# controller.net
KiCad netlist of a schematic drawn in EAGLE
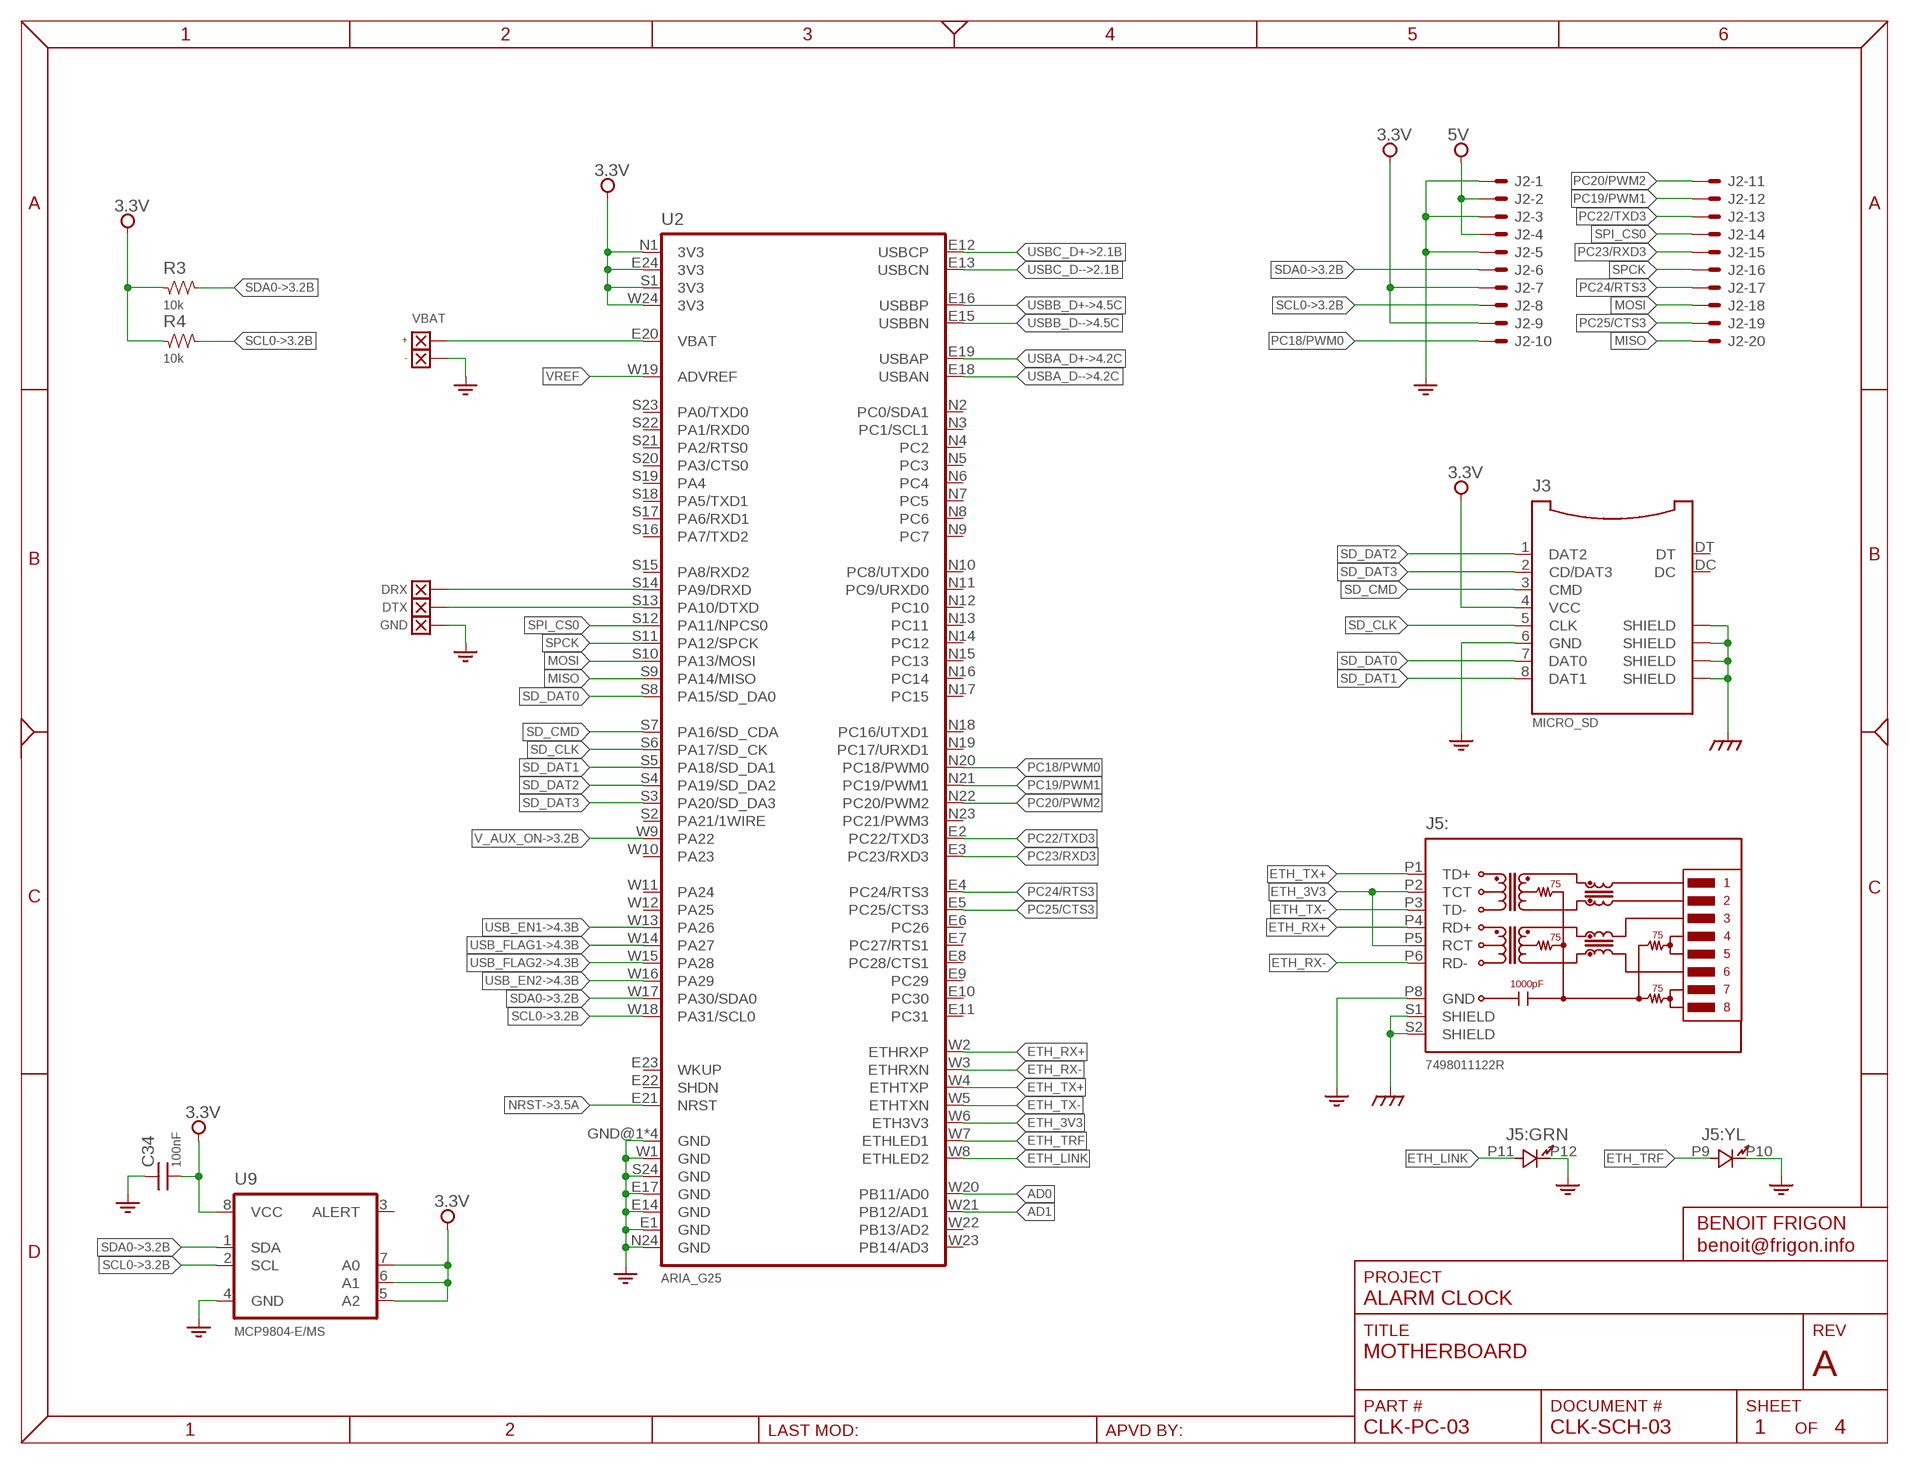
[diagram p0: schematic, sheet 1]
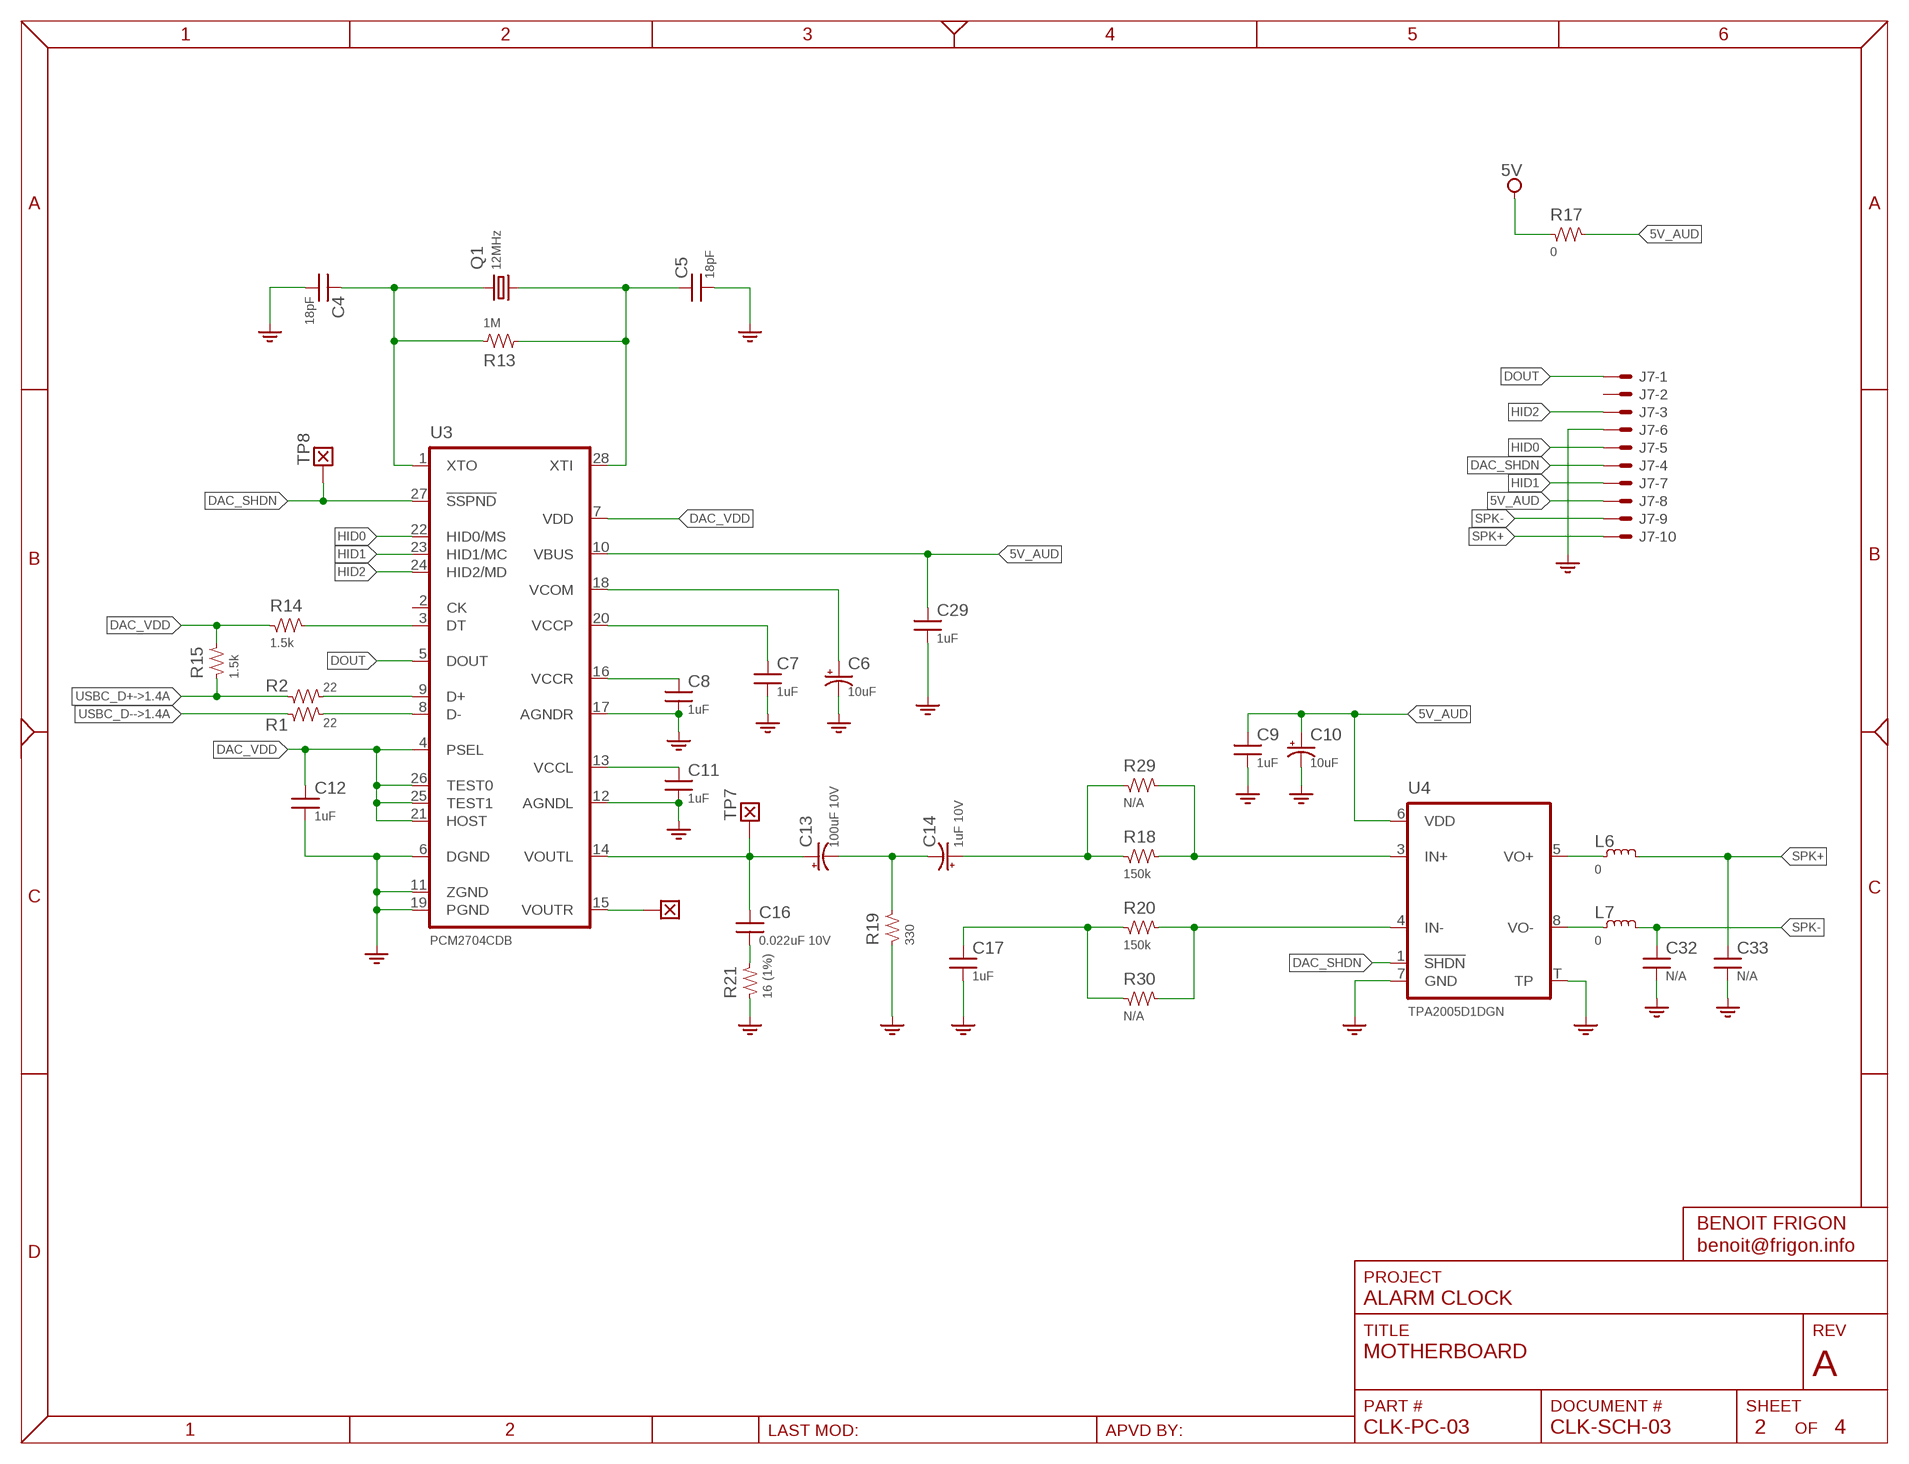
[diagram p1: schematic, sheet 2]
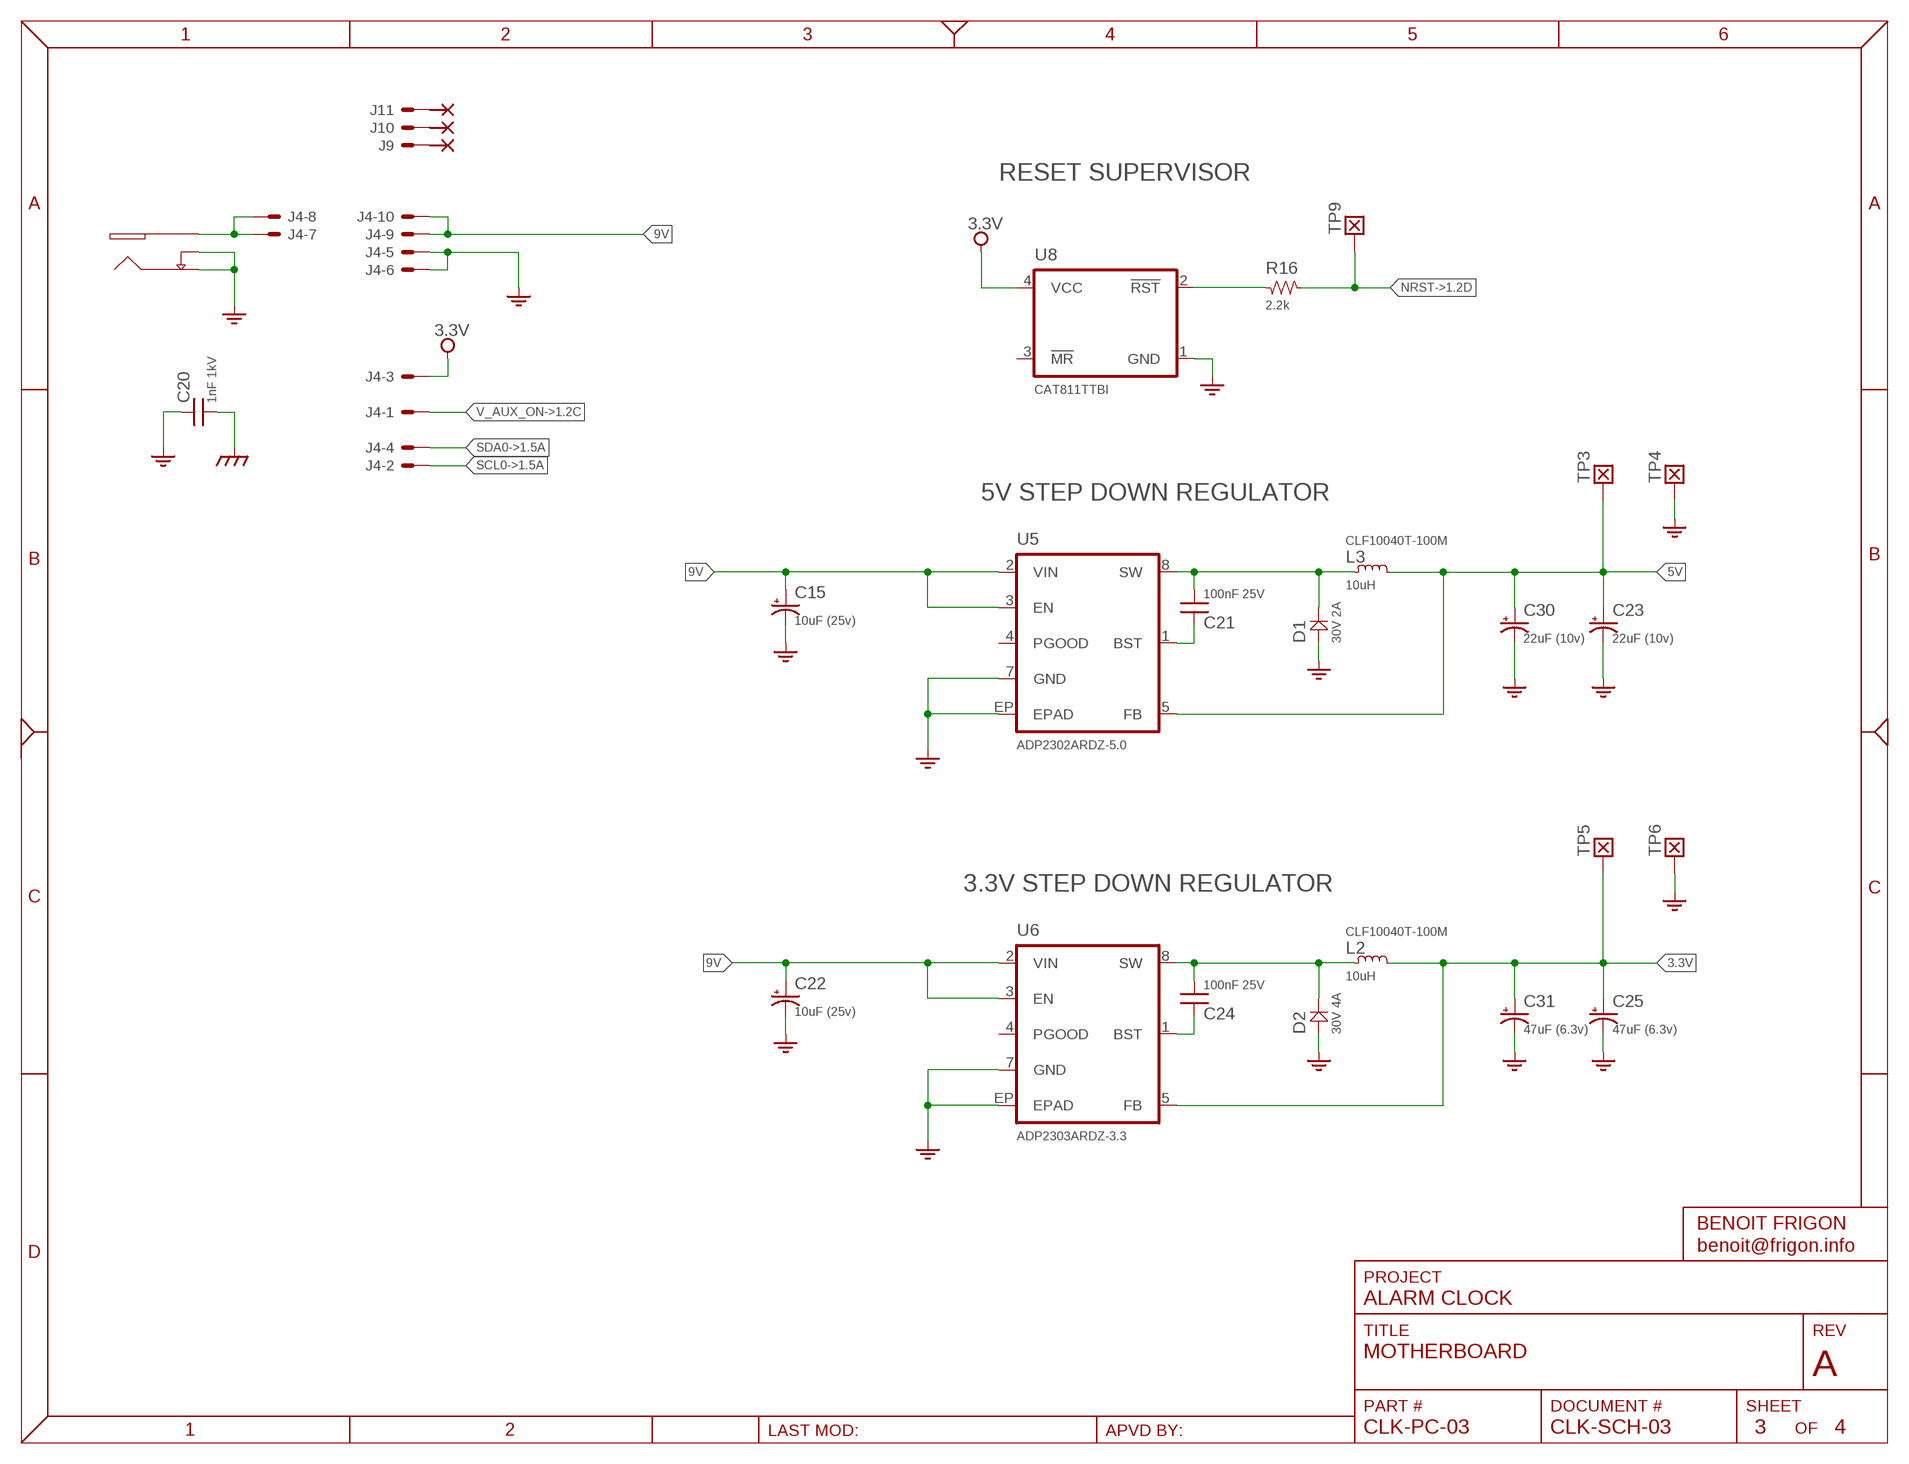
[diagram p2: schematic, sheet 3]
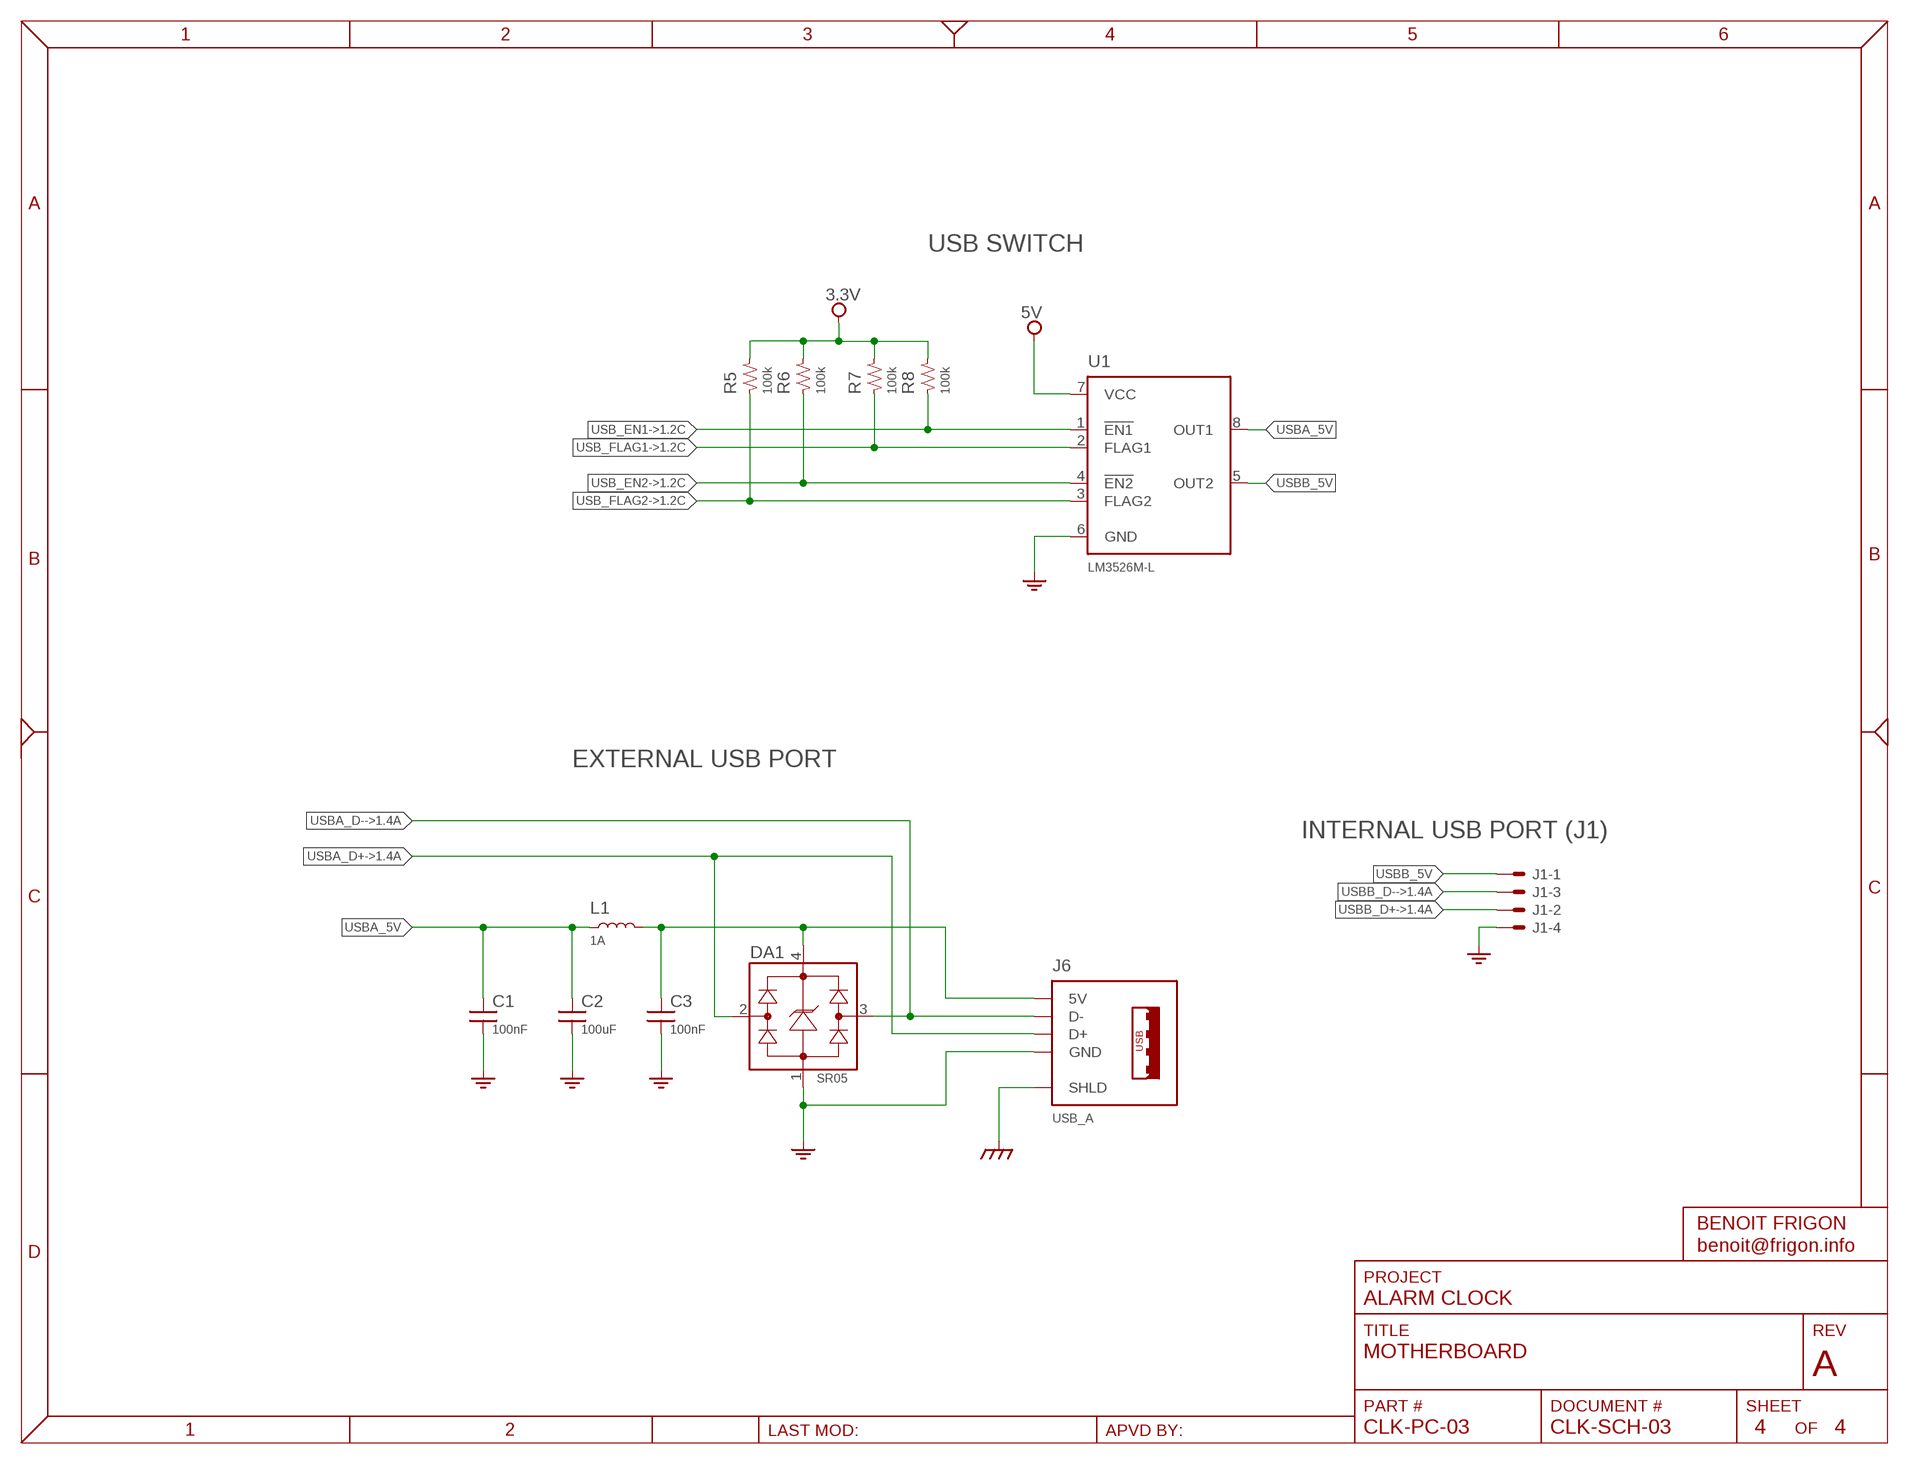
[diagram p3: schematic, sheet 4]

(export (version "E")
  (design (tool "Eeschema 10.0.6"))
  (components
    (comp (ref "C4")
      (value "18pF")
      (footprint "eagle-import:SMD_0603")
      (description "{DESCRIPTION} - SMT 0603 - {value}")
      (fields (field (name "PACKAGE") "SMT 0603"))
      (libsource (lib "eagle-import") (part "CAP-0603"))
    )
    (comp (ref "C5")
      (value "18pF")
      (footprint "eagle-import:SMD_0603")
      (libsource (lib "eagle-import") (part "CAP-0603"))
    )
    (comp (ref "C6")
      (value "10uF")
      (footprint "eagle-import:CAP_S0805")
      (description "Aluminium capacitor - SMT 0805 - {VALUE}")
      (libsource (lib "eagle-import") (part "CAP-E-?-0805ALUM"))
    )
    (comp (ref "C7")
      (value "1uF")
      (footprint "eagle-import:SMD_0603")
      (libsource (lib "eagle-import") (part "CAP-0603"))
    )
    (comp (ref "C8")
      (value "1uF")
      (footprint "eagle-import:SMD_0603")
      (description "{DESCRIPTION} - SMT 0603 - {value}")
      (fields (field (name "PACKAGE") "SMT 0603"))
      (libsource (lib "eagle-import") (part "CAP-0603"))
    )
    (comp (ref "C9")
      (value "1uF")
      (footprint "eagle-import:SMD_0603")
      (libsource (lib "eagle-import") (part "CAP-0603"))
    )
    (comp (ref "C10")
      (value "10uF")
      (footprint "eagle-import:CAP_S0805")
      (description "Aluminium capacitor - SMT 0805 - {VALUE}")
      (libsource (lib "eagle-import") (part "CAP-E-?-0805ALUM"))
    )
    (comp (ref "C11")
      (value "1uF")
      (footprint "eagle-import:SMD_0603")
      (description "{DESCRIPTION} - SMT 0603 - {value}")
      (fields (field (name "PACKAGE") "SMT 0603"))
      (libsource (lib "eagle-import") (part "CAP-0603"))
    )
    (comp (ref "C12")
      (value "1uF")
      (footprint "eagle-import:SMD_0603")
      (libsource (lib "eagle-import") (part "CAP-0603"))
    )
    (comp (ref "C13")
      (value "100uF 10V")
      (footprint "eagle-import:CAP_S1210")
      (description "Aluminium capacitor - SMT 1210 - {VALUE}")
      (fields (field (name "MFG") "AVX"))
      (libsource (lib "eagle-import") (part "CAP-E-?-1210ALUM"))
    )
    (comp (ref "C14")
      (value "1uF 10V")
      (footprint "eagle-import:CAP_S0805")
      (description "Aluminium capacitor - SMT 0805 - {VALUE}")
      (libsource (lib "eagle-import") (part "CAP-E-?-0805ALUM"))
    )
    (comp (ref "C16")
      (value "0.022uF 10V")
      (footprint "eagle-import:SMD_0603")
      (libsource (lib "eagle-import") (part "CAP-0603"))
    )
    (comp (ref "C17")
      (value "1uF")
      (footprint "eagle-import:SMD_0603")
      (libsource (lib "eagle-import") (part "CAP-0603"))
    )
    (comp (ref "C29")
      (value "1uF")
      (footprint "eagle-import:SMD_0603")
      (libsource (lib "eagle-import") (part "CAP-0603"))
    )
    (comp (ref "C32")
      (value "N/A")
      (footprint "eagle-import:SMD_0603")
      (libsource (lib "eagle-import") (part "CAP-0603"))
    )
    (comp (ref "C33")
      (value "N/A")
      (footprint "eagle-import:SMD_0603")
      (libsource (lib "eagle-import") (part "CAP-0603"))
    )
    (comp (ref "J7")
      (value "DL-1.25MM-HEADER-10")
      (footprint "eagle-import:DF13A-10DP-1.25")
      (libsource (lib "eagle-import") (part "DL-1.25MM-HEADER-10"))
    )
    (comp (ref "L6")
      (value "0")
      (footprint "eagle-import:SMD_0603")
      (description "{DESCRIPTION} - SMT 0603 - {VALUE}")
      (libsource (lib "eagle-import") (part "IND?-0603"))
    )
    (comp (ref "L7")
      (value "0")
      (footprint "eagle-import:SMD_0603")
      (description "{DESCRIPTION} - SMT 0603 - {VALUE}")
      (libsource (lib "eagle-import") (part "IND?-0603"))
    )
    (comp (ref "Q1")
      (value "12MHz")
      (footprint "eagle-import:HC49UP")
      (libsource (lib "eagle-import") (part "XTALHC49UP"))
    )
    (comp (ref "R1")
      (value "22")
      (footprint "eagle-import:SMD_0603")
      (libsource (lib "eagle-import") (part "RES-0603"))
    )
    (comp (ref "R2")
      (value "22")
      (footprint "eagle-import:SMD_0603")
      (libsource (lib "eagle-import") (part "RES-0603"))
    )
    (comp (ref "R13")
      (value "1M")
      (footprint "eagle-import:SMD_0603")
      (libsource (lib "eagle-import") (part "RES-0603"))
    )
    (comp (ref "R14")
      (value "1.5k")
      (footprint "eagle-import:SMD_0603")
      (libsource (lib "eagle-import") (part "RES-0603"))
    )
    (comp (ref "R15")
      (value "1.5k")
      (footprint "eagle-import:SMD_0603")
      (libsource (lib "eagle-import") (part "RES-0603"))
    )
    (comp (ref "R17")
      (value "0")
      (footprint "eagle-import:SMD_1206")
      (libsource (lib "eagle-import") (part "RES-1206"))
    )
    (comp (ref "R18")
      (value "150k")
      (footprint "eagle-import:SMD_0603")
      (libsource (lib "eagle-import") (part "RES-0603"))
    )
    (comp (ref "R19")
      (value "330")
      (footprint "eagle-import:SMD_0603")
      (libsource (lib "eagle-import") (part "RES-0603"))
    )
    (comp (ref "R20")
      (value "150k")
      (footprint "eagle-import:SMD_0603")
      (description "{DESCRIPTION} - SMT 0603 - {VALUE}")
      (fields (field (name "PACKAGE") "SMT 0603"))
      (libsource (lib "eagle-import") (part "RES-0603"))
    )
    (comp (ref "R21")
      (value "16 (1%)")
      (footprint "eagle-import:SMD_0603")
      (libsource (lib "eagle-import") (part "RES-0603"))
    )
    (comp (ref "R29")
      (value "N/A")
      (footprint "eagle-import:SMD_0603")
      (description "{DESCRIPTION} - SMT 0603 - {VALUE}")
      (fields (field (name "PACKAGE") "SMT 0603"))
      (libsource (lib "eagle-import") (part "RES-0603"))
    )
    (comp (ref "R30")
      (value "N/A")
      (footprint "eagle-import:SMD_0603")
      (description "{DESCRIPTION} - SMT 0603 - {VALUE}")
      (fields (field (name "PACKAGE") "SMT 0603"))
      (libsource (lib "eagle-import") (part "RES-0603"))
    )
    (comp (ref "TP7")
      (value "TEST_POINT-050")
      (footprint "eagle-import:TP_050")
      (libsource (lib "eagle-import") (part "TEST_POINT-050"))
    )
    (comp (ref "TP8")
      (value "TEST_POINT-050")
      (footprint "eagle-import:TP_050")
      (libsource (lib "eagle-import") (part "TEST_POINT-050"))
    )
    (comp (ref "U3")
      (value "PCM2704CDB")
      (footprint "eagle-import:SSOP28")
      (libsource (lib "eagle-import") (part "PCM2704CDB"))
    )
    (comp (ref "U4")
      (value "TPA2005D1DGN")
      (footprint "eagle-import:PPSOP8")
      (libsource (lib "eagle-import") (part "TPA2005D1?DGN"))
    )
    (comp (ref "W1")
      (value "WIRE-150X75")
      (footprint "eagle-import:WIRE_SMT_150X75")
      (libsource (lib "eagle-import") (part "WIRE-?150X75"))
    )
    (comp (ref "C15")
      (value "10uF (25v)")
      (footprint "eagle-import:CAP_S1210")
      (fields (field (name "MFG") "AVX") (field (name "PART_NO") "TPSB106K025R1800"))
      (libsource (lib "eagle-import") (part "CAP-E-?-1210TANT"))
    )
    (comp (ref "C20")
      (value "1nF 1kV")
      (footprint "eagle-import:SMD_0805")
      (libsource (lib "eagle-import") (part "CAP-0805"))
    )
    (comp (ref "C21")
      (value "100nF 25V")
      (footprint "eagle-import:SMD_0603")
      (libsource (lib "eagle-import") (part "CAP-0603"))
    )
    (comp (ref "C22")
      (value "10uF (25v)")
      (footprint "eagle-import:CAP_S1210")
      (fields (field (name "MFG") "AVX") (field (name "PART_NO") "TPSB106K025R1800"))
      (libsource (lib "eagle-import") (part "CAP-E-?-1210TANT"))
    )
    (comp (ref "C23")
      (value "22uF (10v)")
      (footprint "eagle-import:CAP_S1206")
      (description "Tantalum capacitor - SMT 1206 - {VALUE}")
      (fields (field (name "MFG") "AVX") (field (name "PART_NO") "TPSA226M010R0900"))
      (libsource (lib "eagle-import") (part "CAP-E-?-1206TANT"))
    )
    (comp (ref "C24")
      (value "100nF 25V")
      (footprint "eagle-import:SMD_0603")
      (libsource (lib "eagle-import") (part "CAP-0603"))
    )
    (comp (ref "C25")
      (value "47uF (6.3v)")
      (footprint "eagle-import:CAP_S1206")
      (description "Tantalum capacitor - SMT 1206 - {VALUE}")
      (fields (field (name "MFG") "AVX") (field (name "PART_NO") "TPSA476K006R0800"))
      (libsource (lib "eagle-import") (part "CAP-E-?-1206TANT"))
    )
    (comp (ref "C30")
      (value "22uF (10v)")
      (footprint "eagle-import:CAP_S1206")
      (description "Tantalum capacitor - SMT 1206 - {VALUE}")
      (fields (field (name "MFG") "AVX") (field (name "PART_NO") "TPSA226M010R0900"))
      (libsource (lib "eagle-import") (part "CAP-E-?-1206TANT"))
    )
    (comp (ref "C31")
      (value "47uF (6.3v)")
      (footprint "eagle-import:CAP_S1206")
      (description "Tantalum capacitor - SMT 1206 - {VALUE}")
      (fields (field (name "MFG") "AVX") (field (name "PART_NO") "TPSA476K006R0800"))
      (libsource (lib "eagle-import") (part "CAP-E-?-1206TANT"))
    )
    (comp (ref "D1")
      (value "30V 2A")
      (footprint "eagle-import:DIODE_DO214-AA")
      (libsource (lib "eagle-import") (part "DIODE-DO214-AA"))
    )
    (comp (ref "D2")
      (value "30V 4A")
      (footprint "eagle-import:DIODE_DO214-AA")
      (libsource (lib "eagle-import") (part "DIODE-DO214-AA"))
    )
    (comp (ref "J4")
      (value "DL-100-HEADER-10-V")
      (footprint "eagle-import:534206-5")
      (description "{DESCRIPTION} Receptacle - Vertical")
      (fields (field (name "MFG") "Tyco Electronics") (field (name "SKU") "534206-5"))
      (libsource (lib "eagle-import") (part "DL-100-HEADER-10-V"))
    )
    (comp (ref "J8")
      (value "CUI-PJ-013C")
      (footprint "eagle-import:CUI-PJ-013C")
      (libsource (lib "eagle-import") (part "CUI-PJ-013C"))
    )
    (comp (ref "J9")
      (value "SNG-100-HEADER-01-HDR-V")
      (footprint "eagle-import:HDR_M_1")
      (libsource (lib "eagle-import") (part "SNG-100-HEADER-01-HDR-V"))
    )
    (comp (ref "J10")
      (value "SNG-100-HEADER-01-HDR-V")
      (footprint "eagle-import:HDR_M_1")
      (libsource (lib "eagle-import") (part "SNG-100-HEADER-01-HDR-V"))
    )
    (comp (ref "J11")
      (value "SNG-100-HEADER-01-HDR-V")
      (footprint "eagle-import:HDR_M_1")
      (libsource (lib "eagle-import") (part "SNG-100-HEADER-01-HDR-V"))
    )
    (comp (ref "L2")
      (value "10uH")
      (footprint "eagle-import:IND-10X10")
      (fields (field (name "PART_NO") "CLF10040T-100M"))
      (libsource (lib "eagle-import") (part "IND?-10X10"))
    )
    (comp (ref "L3")
      (value "10uH")
      (footprint "eagle-import:IND-10X10")
      (fields (field (name "MFG") "TDK") (field (name "PART_NO") "CLF10040T-100M"))
      (libsource (lib "eagle-import") (part "IND?-10X10"))
    )
    (comp (ref "R16")
      (value "2.2k")
      (footprint "eagle-import:SMD_0603")
      (libsource (lib "eagle-import") (part "RES-0603"))
    )
    (comp (ref "TP3")
      (value "TEST_POINT-050")
      (footprint "eagle-import:TP_050")
      (libsource (lib "eagle-import") (part "TEST_POINT-050"))
    )
    (comp (ref "TP4")
      (value "TEST_POINT-050")
      (footprint "eagle-import:TP_050")
      (libsource (lib "eagle-import") (part "TEST_POINT-050"))
    )
    (comp (ref "TP5")
      (value "TEST_POINT-050")
      (footprint "eagle-import:TP_050")
      (fields (field (name "BOM") "FALSE"))
      (libsource (lib "eagle-import") (part "TEST_POINT-050"))
    )
    (comp (ref "TP6")
      (value "TEST_POINT-050")
      (footprint "eagle-import:TP_050")
      (fields (field (name "BOM") "FALSE"))
      (libsource (lib "eagle-import") (part "TEST_POINT-050"))
    )
    (comp (ref "TP9")
      (value "TEST_POINT-050")
      (footprint "eagle-import:TP_050")
      (libsource (lib "eagle-import") (part "TEST_POINT-050"))
    )
    (comp (ref "U5")
      (value "ADP2302ARDZ-5.0")
      (footprint "eagle-import:SOIC8-EP")
      (description "{DESCRIPTION} - 2A, 5V")
      (fields (field (name "MFG") "Analog Devices"))
      (libsource (lib "eagle-import") (part "ADP230?2ARDZ-5.0"))
    )
    (comp (ref "U6")
      (value "ADP2303ARDZ-3.3")
      (footprint "eagle-import:SOIC8-EP")
      (description "{DESCRIPTION} - 3A, 3.3v")
      (fields (field (name "MFG") "Analog Devices"))
      (libsource (lib "eagle-import") (part "ADP230?3ARDZ-3.3"))
    )
    (comp (ref "U8")
      (value "CAT811TTBI")
      (footprint "eagle-import:SOT143")
      (description "{DESCRIPTION} - 3.08V threshold")
      (fields (field (name "MFG") "ON Semiconductors"))
      (libsource (lib "eagle-import") (part "CAT811?TBIT"))
    )
    (comp (ref "C34")
      (value "100nF")
      (footprint "eagle-import:SMD_0603")
      (libsource (lib "eagle-import") (part "CAP-0603"))
    )
    (comp (ref "J2")
      (value "DL-1.25MM-HEADER-20")
      (footprint "eagle-import:DF13A-20DP-1.25")
      (libsource (lib "eagle-import") (part "DL-1.25MM-HEADER-20"))
    )
    (comp (ref "J3")
      (value "MICRO_SD")
      (footprint "eagle-import:5027020891")
      (libsource (lib "eagle-import") (part "MICRO_SD"))
    )
    (comp (ref "J5")
      (value "7498011122R")
      (footprint "eagle-import:7498011122R")
      (libsource (lib "eagle-import") (part "7498011122R"))
    )
    (comp (ref "R3")
      (value "10k")
      (footprint "eagle-import:SMD_0603")
      (description "{DESCRIPTION} - SMT 0603 - {VALUE}")
      (fields (field (name "PACKAGE") "SMT 0603"))
      (libsource (lib "eagle-import") (part "RES-0603"))
    )
    (comp (ref "R4")
      (value "10k")
      (footprint "eagle-import:SMD_0603")
      (description "{DESCRIPTION} - SMT 0603 - {VALUE}")
      (fields (field (name "PACKAGE") "SMT 0603"))
      (libsource (lib "eagle-import") (part "RES-0603"))
    )
    (comp (ref "TP1")
      (value "+")
      (footprint "eagle-import:WIRE_SMT_150X75")
      (libsource (lib "eagle-import") (part "WIRE-?150X75"))
    )
    (comp (ref "TP2")
      (value "-")
      (footprint "eagle-import:WIRE_SMT_150X75")
      (libsource (lib "eagle-import") (part "WIRE-?150X75"))
    )
    (comp (ref "U2")
      (value "ARIA_G25")
      (footprint "eagle-import:ARIA_G25")
      (libsource (lib "eagle-import") (part "ARIA_G25"))
    )
    (comp (ref "U9")
      (value "MCP9804-E/MS")
      (footprint "eagle-import:MSOP8")
      (fields (field (name "MFG") "Microchip"))
      (libsource (lib "eagle-import") (part "MCP9804-/?MSE"))
    )
    (comp (ref "W2")
      (value "DRX")
      (footprint "eagle-import:WIRE_SMT_150X75")
      (libsource (lib "eagle-import") (part "WIRE-?150X75"))
    )
    (comp (ref "W3")
      (value "DTX")
      (footprint "eagle-import:WIRE_SMT_150X75")
      (libsource (lib "eagle-import") (part "WIRE-?150X75"))
    )
    (comp (ref "W4")
      (value "GND")
      (footprint "eagle-import:WIRE_SMT_150X75")
      (libsource (lib "eagle-import") (part "WIRE-?150X75"))
    )
    (comp (ref "C1")
      (value "100nF")
      (footprint "eagle-import:SMD_0603")
      (libsource (lib "eagle-import") (part "CAP-0603"))
    )
    (comp (ref "C2")
      (value "100uF")
      (footprint "eagle-import:SMD_0805")
      (libsource (lib "eagle-import") (part "CAP-0805"))
    )
    (comp (ref "C3")
      (value "100nF")
      (footprint "eagle-import:SMD_0603")
      (libsource (lib "eagle-import") (part "CAP-0603"))
    )
    (comp (ref "DA1")
      (value "SR05")
      (footprint "eagle-import:SOT143")
      (fields (field (name "MFG") "Semtech"))
      (libsource (lib "eagle-import") (part "SR05"))
    )
    (comp (ref "J1")
      (value "SNG-2MM-HEADER-04-V")
      (footprint "eagle-import:DF3X-4P-2DSA")
      (description "{DESCRIPTION} - Vertical")
      (fields (field (name "MFG") "Hirose Electronic") (field (name "SKU") "DF3A-4P-2DSA"))
      (libsource (lib "eagle-import") (part "SNG-2MM-HEADER-04-V"))
    )
    (comp (ref "J6")
      (value "USB_A")
      (footprint "eagle-import:292303-1")
      (libsource (lib "eagle-import") (part "USB_A"))
    )
    (comp (ref "L1")
      (value "1A")
      (footprint "eagle-import:SMD_0805")
      (libsource (lib "eagle-import") (part "FERRITE"))
    )
    (comp (ref "R5")
      (value "100k")
      (footprint "eagle-import:SMD_0603")
      (description "{DESCRIPTION} - SMT 0603 - {VALUE}")
      (fields (field (name "PACKAGE") "SMT 0603"))
      (libsource (lib "eagle-import") (part "RES-0603"))
    )
    (comp (ref "R6")
      (value "100k")
      (footprint "eagle-import:SMD_0603")
      (description "{DESCRIPTION} - SMT 0603 - {VALUE}")
      (fields (field (name "PACKAGE") "SMT 0603"))
      (libsource (lib "eagle-import") (part "RES-0603"))
    )
    (comp (ref "R7")
      (value "100k")
      (footprint "eagle-import:SMD_0603")
      (description "{DESCRIPTION} - SMT 0603 - {VALUE}")
      (fields (field (name "PACKAGE") "SMT 0603"))
      (libsource (lib "eagle-import") (part "RES-0603"))
    )
    (comp (ref "R8")
      (value "100k")
      (footprint "eagle-import:SMD_0603")
      (description "{DESCRIPTION} - SMT 0603 - {VALUE}")
      (fields (field (name "PACKAGE") "SMT 0603"))
      (libsource (lib "eagle-import") (part "RES-0603"))
    )
    (comp (ref "U1")
      (value "LM3526M-L")
      (footprint "eagle-import:SOIC8")
      (fields (field (name "MFG") "National Semiconductors"))
      (libsource (lib "eagle-import") (part "LM3526?-ML"))
    )
  )
  (nets
    (net (code "1") (name "3.3V") (class "Default")
      (node (ref "C25") (pin "+") (pinfunction "+_+") (pintype "passive"))
      (node (ref "C31") (pin "+") (pinfunction "+_+") (pintype "passive"))
      (node (ref "C34") (pin "2") (pinfunction "2_2") (pintype "passive"))
      (node (ref "J2") (pin "7") (pinfunction "S_7") (pintype "bidirectional"))
      (node (ref "J2") (pin "9") (pinfunction "S_9") (pintype "bidirectional"))
      (node (ref "J3") (pin "4") (pinfunction "VCC_4") (pintype "power_in"))
      (node (ref "J4") (pin "3") (pinfunction "S_3") (pintype "bidirectional"))
      (node (ref "L2") (pin "2") (pinfunction "2_2") (pintype "passive"))
      (node (ref "R3") (pin "1") (pinfunction "1_1") (pintype "passive"))
      (node (ref "R4") (pin "1") (pinfunction "1_1") (pintype "passive"))
      (node (ref "R5") (pin "2") (pinfunction "2_2") (pintype "passive"))
      (node (ref "R6") (pin "2") (pinfunction "2_2") (pintype "passive"))
      (node (ref "R7") (pin "2") (pinfunction "2_2") (pintype "passive"))
      (node (ref "R8") (pin "2") (pinfunction "2_2") (pintype "passive"))
      (node (ref "TP5") (pin "1") (pinfunction "P$1_1") (pintype "bidirectional"))
      (node (ref "U2") (pin "E24") (pinfunction "3V3_E24") (pintype "power_in"))
      (node (ref "U2") (pin "N1") (pinfunction "3V3_N1") (pintype "power_in"))
      (node (ref "U2") (pin "S1") (pinfunction "3V3_S1") (pintype "power_in"))
      (node (ref "U2") (pin "W24") (pinfunction "3V3_W24") (pintype "power_in"))
      (node (ref "U6") (pin "5") (pinfunction "FB_5") (pintype "bidirectional"))
      (node (ref "U8") (pin "4") (pinfunction "VCC_4") (pintype "power_in"))
      (node (ref "U9") (pin "5") (pinfunction "A2_5") (pintype "bidirectional"))
      (node (ref "U9") (pin "6") (pinfunction "A1_6") (pintype "bidirectional"))
      (node (ref "U9") (pin "7") (pinfunction "A0_7") (pintype "bidirectional"))
      (node (ref "U9") (pin "8") (pinfunction "VCC_8") (pintype "power_in"))
    )
    (net (code "2") (name "5V") (class "Default")
      (node (ref "C23") (pin "+") (pinfunction "+_+") (pintype "passive"))
      (node (ref "C30") (pin "+") (pinfunction "+_+") (pintype "passive"))
      (node (ref "J2") (pin "2") (pinfunction "S_2") (pintype "bidirectional"))
      (node (ref "J2") (pin "4") (pinfunction "S_4") (pintype "bidirectional"))
      (node (ref "L3") (pin "2") (pinfunction "2_2") (pintype "passive"))
      (node (ref "R17") (pin "1") (pinfunction "1_1") (pintype "passive"))
      (node (ref "TP3") (pin "1") (pinfunction "P$1_1") (pintype "bidirectional"))
      (node (ref "U1") (pin "7") (pinfunction "VCC_7") (pintype "bidirectional"))
      (node (ref "U5") (pin "5") (pinfunction "FB_5") (pintype "bidirectional"))
    )
    (net (code "3") (name "5V_AUD") (class "Default")
      (node (ref "C10") (pin "+") (pinfunction "+_+") (pintype "passive"))
      (node (ref "C29") (pin "1") (pinfunction "1_1") (pintype "passive"))
      (node (ref "C9") (pin "1") (pinfunction "1_1") (pintype "passive"))
      (node (ref "J7") (pin "8") (pinfunction "S_8") (pintype "bidirectional"))
      (node (ref "R17") (pin "2") (pinfunction "2_2") (pintype "passive"))
      (node (ref "U3") (pin "10") (pinfunction "VBUS_10") (pintype "bidirectional"))
      (node (ref "U4") (pin "6") (pinfunction "VDD_6") (pintype "bidirectional"))
    )
    (net (code "4") (name "9V") (class "Default")
      (node (ref "C15") (pin "+") (pinfunction "+_+") (pintype "passive"))
      (node (ref "C22") (pin "+") (pinfunction "+_+") (pintype "passive"))
      (node (ref "J4") (pin "10") (pinfunction "S_10") (pintype "bidirectional"))
      (node (ref "J4") (pin "9") (pinfunction "S_9") (pintype "bidirectional"))
      (node (ref "U5") (pin "2") (pinfunction "VIN_2") (pintype "bidirectional"))
      (node (ref "U5") (pin "3") (pinfunction "EN_3") (pintype "bidirectional"))
      (node (ref "U6") (pin "2") (pinfunction "VIN_2") (pintype "bidirectional"))
      (node (ref "U6") (pin "3") (pinfunction "EN_3") (pintype "bidirectional"))
    )
    (net (code "5") (name "AD0") (class "Default")
      (node (ref "U2") (pin "W20") (pinfunction "PB11/AD0_W20") (pintype "bidirectional"))
    )
    (net (code "6") (name "AD1") (class "Default")
      (node (ref "U2") (pin "W21") (pinfunction "PB12/AD1_W21") (pintype "bidirectional"))
    )
    (net (code "7") (name "DAC_SHDN") (class "Default")
      (node (ref "J7") (pin "4") (pinfunction "S_4") (pintype "bidirectional"))
      (node (ref "TP8") (pin "1") (pinfunction "P$1_1") (pintype "bidirectional"))
      (node (ref "U3") (pin "27") (pinfunction "~{SSPND}_27") (pintype "bidirectional"))
      (node (ref "U4") (pin "1") (pinfunction "~{SHDN}_1") (pintype "bidirectional"))
    )
    (net (code "8") (name "DAC_VDD") (class "Default")
      (node (ref "C12") (pin "1") (pinfunction "1_1") (pintype "passive"))
      (node (ref "R14") (pin "1") (pinfunction "1_1") (pintype "passive"))
      (node (ref "R15") (pin "2") (pinfunction "2_2") (pintype "passive"))
      (node (ref "U3") (pin "21") (pinfunction "HOST_21") (pintype "bidirectional"))
      (node (ref "U3") (pin "25") (pinfunction "TEST1_25") (pintype "bidirectional"))
      (node (ref "U3") (pin "26") (pinfunction "TEST0_26") (pintype "bidirectional"))
      (node (ref "U3") (pin "4") (pinfunction "PSEL_4") (pintype "bidirectional"))
      (node (ref "U3") (pin "7") (pinfunction "VDD_7") (pintype "bidirectional"))
    )
    (net (code "9") (name "DOUT") (class "Default")
      (node (ref "J7") (pin "1") (pinfunction "S_1") (pintype "bidirectional"))
      (node (ref "U3") (pin "5") (pinfunction "DOUT_5") (pintype "bidirectional"))
    )
    (net (code "10") (name "EARTH") (class "Default")
      (node (ref "C20") (pin "2") (pinfunction "2_2") (pintype "passive"))
      (node (ref "J3") (pin "SHDL@3") (pinfunction "SHIELD_SHDL@3") (pintype "power_in"))
      (node (ref "J3") (pin "SHLD@1") (pinfunction "SHIELD_SHLD@1") (pintype "power_in"))
      (node (ref "J3") (pin "SHLD@2") (pinfunction "SHIELD_SHLD@2") (pintype "power_in"))
      (node (ref "J3") (pin "SHLD@4") (pinfunction "SHIELD_SHLD@4") (pintype "power_in"))
      (node (ref "J5") (pin "S1") (pinfunction "SHIELD_S1") (pintype "bidirectional"))
      (node (ref "J5") (pin "S2") (pinfunction "SHIELD_S2") (pintype "bidirectional"))
      (node (ref "J6") (pin "SHLD@1") (pinfunction "SHLD_SHLD@1") (pintype "bidirectional"))
      (node (ref "J6") (pin "SHLD@2") (pinfunction "SHLD_SHLD@2") (pintype "bidirectional"))
    )
    (net (code "11") (name "ETH_3V3") (class "Default")
      (node (ref "J5") (pin "P2") (pinfunction "TCT_P2") (pintype "bidirectional"))
      (node (ref "J5") (pin "P5") (pinfunction "RCT_P5") (pintype "bidirectional"))
      (node (ref "U2") (pin "W6") (pinfunction "ETH3V3_W6") (pintype "bidirectional"))
    )
    (net (code "12") (name "ETH_LINK") (class "Default")
      (node (ref "J5") (pin "P11") (pinfunction "A_P11") (pintype "bidirectional"))
      (node (ref "U2") (pin "W8") (pinfunction "ETHLED2_W8") (pintype "bidirectional"))
    )
    (net (code "13") (name "ETH_RX+") (class "Default")
      (node (ref "J5") (pin "P4") (pinfunction "RD+_P4") (pintype "bidirectional"))
      (node (ref "U2") (pin "W2") (pinfunction "ETHRXP_W2") (pintype "bidirectional"))
    )
    (net (code "14") (name "ETH_RX-") (class "Default")
      (node (ref "J5") (pin "P6") (pinfunction "RD-_P6") (pintype "bidirectional"))
      (node (ref "U2") (pin "W3") (pinfunction "ETHRXN_W3") (pintype "bidirectional"))
    )
    (net (code "15") (name "ETH_TRF") (class "Default")
      (node (ref "J5") (pin "P9") (pinfunction "A_P9") (pintype "bidirectional"))
      (node (ref "U2") (pin "W7") (pinfunction "ETHLED1_W7") (pintype "bidirectional"))
    )
    (net (code "16") (name "ETH_TX+") (class "Default")
      (node (ref "J5") (pin "P1") (pinfunction "TD+_P1") (pintype "bidirectional"))
      (node (ref "U2") (pin "W4") (pinfunction "ETHTXP_W4") (pintype "bidirectional"))
    )
    (net (code "17") (name "ETH_TX-") (class "Default")
      (node (ref "J5") (pin "P3") (pinfunction "TD-_P3") (pintype "bidirectional"))
      (node (ref "U2") (pin "W5") (pinfunction "ETHTXN_W5") (pintype "bidirectional"))
    )
    (net (code "18") (name "GND") (class "Default")
      (node (ref "C1") (pin "2") (pinfunction "2_2") (pintype "passive"))
      (node (ref "C10") (pin "-") (pinfunction "-_-") (pintype "passive"))
      (node (ref "C11") (pin "2") (pinfunction "2_2") (pintype "passive"))
      (node (ref "C12") (pin "2") (pinfunction "2_2") (pintype "passive"))
      (node (ref "C15") (pin "-") (pinfunction "-_-") (pintype "passive"))
      (node (ref "C17") (pin "2") (pinfunction "2_2") (pintype "passive"))
      (node (ref "C2") (pin "2") (pinfunction "2_2") (pintype "passive"))
      (node (ref "C20") (pin "1") (pinfunction "1_1") (pintype "passive"))
      (node (ref "C22") (pin "-") (pinfunction "-_-") (pintype "passive"))
      (node (ref "C23") (pin "-") (pinfunction "-_-") (pintype "passive"))
      (node (ref "C25") (pin "-") (pinfunction "-_-") (pintype "passive"))
      (node (ref "C29") (pin "2") (pinfunction "2_2") (pintype "passive"))
      (node (ref "C3") (pin "2") (pinfunction "2_2") (pintype "passive"))
      (node (ref "C30") (pin "-") (pinfunction "-_-") (pintype "passive"))
      (node (ref "C31") (pin "-") (pinfunction "-_-") (pintype "passive"))
      (node (ref "C32") (pin "2") (pinfunction "2_2") (pintype "passive"))
      (node (ref "C33") (pin "2") (pinfunction "2_2") (pintype "passive"))
      (node (ref "C34") (pin "1") (pinfunction "1_1") (pintype "passive"))
      (node (ref "C4") (pin "2") (pinfunction "2_2") (pintype "passive"))
      (node (ref "C5") (pin "2") (pinfunction "2_2") (pintype "passive"))
      (node (ref "C6") (pin "-") (pinfunction "-_-") (pintype "passive"))
      (node (ref "C7") (pin "2") (pinfunction "2_2") (pintype "passive"))
      (node (ref "C8") (pin "2") (pinfunction "2_2") (pintype "passive"))
      (node (ref "C9") (pin "2") (pinfunction "2_2") (pintype "passive"))
      (node (ref "D1") (pin "A") (pinfunction "A_A") (pintype "passive"))
      (node (ref "D2") (pin "A") (pinfunction "A_A") (pintype "passive"))
      (node (ref "DA1") (pin "1") (pinfunction "1_1") (pintype "passive"))
      (node (ref "J1") (pin "4") (pinfunction "S_4") (pintype "bidirectional"))
      (node (ref "J2") (pin "1") (pinfunction "S_1") (pintype "bidirectional"))
      (node (ref "J2") (pin "3") (pinfunction "S_3") (pintype "bidirectional"))
      (node (ref "J2") (pin "5") (pinfunction "S_5") (pintype "bidirectional"))
      (node (ref "J3") (pin "6") (pinfunction "GND_6") (pintype "power_in"))
      (node (ref "J4") (pin "5") (pinfunction "S_5") (pintype "bidirectional"))
      (node (ref "J4") (pin "6") (pinfunction "S_6") (pintype "bidirectional"))
      (node (ref "J5") (pin "P10") (pinfunction "K_P10") (pintype "bidirectional"))
      (node (ref "J5") (pin "P12") (pinfunction "K_P12") (pintype "bidirectional"))
      (node (ref "J5") (pin "P8") (pinfunction "GND_P8") (pintype "bidirectional"))
      (node (ref "J6") (pin "4") (pinfunction "GND_4") (pintype "power_in"))
      (node (ref "J7") (pin "6") (pinfunction "S_6") (pintype "bidirectional"))
      (node (ref "J8") (pin "2") (pinfunction "GND_2") (pintype "bidirectional"))
      (node (ref "J8") (pin "3") (pinfunction "SW_3") (pintype "bidirectional"))
      (node (ref "R19") (pin "1") (pinfunction "1_1") (pintype "passive"))
      (node (ref "R21") (pin "1") (pinfunction "1_1") (pintype "passive"))
      (node (ref "TP2") (pin "1") (pinfunction "P$1_1") (pintype "bidirectional"))
      (node (ref "TP4") (pin "1") (pinfunction "P$1_1") (pintype "bidirectional"))
      (node (ref "TP6") (pin "1") (pinfunction "P$1_1") (pintype "bidirectional"))
      (node (ref "U1") (pin "6") (pinfunction "GND_6") (pintype "bidirectional"))
      (node (ref "U2") (pin "E1") (pinfunction "GND_E1") (pintype "power_in"))
      (node (ref "U2") (pin "E14") (pinfunction "GND_E14") (pintype "power_in"))
      (node (ref "U2") (pin "E17") (pinfunction "GND_E17") (pintype "power_in"))
      (node (ref "U2") (pin "GND@1") (pinfunction "GND_GND@1") (pintype "power_in"))
      (node (ref "U2") (pin "GND@2") (pinfunction "GND_GND@2") (pintype "power_in"))
      (node (ref "U2") (pin "GND@3") (pinfunction "GND_GND@3") (pintype "power_in"))
      (node (ref "U2") (pin "GND@4") (pinfunction "GND_GND@4") (pintype "power_in"))
      (node (ref "U2") (pin "N24") (pinfunction "GND_N24") (pintype "power_in"))
      (node (ref "U2") (pin "S24") (pinfunction "GND_S24") (pintype "power_in"))
      (node (ref "U2") (pin "W1") (pinfunction "GND_W1") (pintype "power_in"))
      (node (ref "U3") (pin "11") (pinfunction "ZGND_11") (pintype "bidirectional"))
      (node (ref "U3") (pin "12") (pinfunction "AGNDL_12") (pintype "bidirectional"))
      (node (ref "U3") (pin "17") (pinfunction "AGNDR_17") (pintype "bidirectional"))
      (node (ref "U3") (pin "19") (pinfunction "PGND_19") (pintype "bidirectional"))
      (node (ref "U3") (pin "6") (pinfunction "DGND_6") (pintype "bidirectional"))
      (node (ref "U4") (pin "7") (pinfunction "GND_7") (pintype "bidirectional"))
      (node (ref "U4") (pin "T") (pinfunction "TP_T") (pintype "bidirectional"))
      (node (ref "U5") (pin "7") (pinfunction "GND_7") (pintype "bidirectional"))
      (node (ref "U5") (pin "EP") (pinfunction "EPAD_EP") (pintype "bidirectional"))
      (node (ref "U6") (pin "7") (pinfunction "GND_7") (pintype "bidirectional"))
      (node (ref "U6") (pin "EP") (pinfunction "EPAD_EP") (pintype "bidirectional"))
      (node (ref "U8") (pin "1") (pinfunction "GND_1") (pintype "power_in"))
      (node (ref "U9") (pin "4") (pinfunction "GND_4") (pintype "power_in"))
      (node (ref "W4") (pin "1") (pinfunction "P$1_1") (pintype "bidirectional"))
    )
    (net (code "19") (name "HID0") (class "Default")
      (node (ref "J7") (pin "5") (pinfunction "S_5") (pintype "bidirectional"))
      (node (ref "U3") (pin "22") (pinfunction "HID0/MS_22") (pintype "bidirectional"))
    )
    (net (code "20") (name "HID1") (class "Default")
      (node (ref "J7") (pin "7") (pinfunction "S_7") (pintype "bidirectional"))
      (node (ref "U3") (pin "23") (pinfunction "HID1/MC_23") (pintype "bidirectional"))
    )
    (net (code "21") (name "HID2") (class "Default")
      (node (ref "J7") (pin "3") (pinfunction "S_3") (pintype "bidirectional"))
      (node (ref "U3") (pin "24") (pinfunction "HID2/MD_24") (pintype "bidirectional"))
    )
    (net (code "22") (name "MISO") (class "Default")
      (node (ref "J2") (pin "20") (pinfunction "S_20") (pintype "bidirectional"))
      (node (ref "U2") (pin "S9") (pinfunction "PA14/MISO_S9") (pintype "bidirectional"))
    )
    (net (code "23") (name "MOSI") (class "Default")
      (node (ref "J2") (pin "18") (pinfunction "S_18") (pintype "bidirectional"))
      (node (ref "U2") (pin "S10") (pinfunction "PA13/MOSI_S10") (pintype "bidirectional"))
    )
    (net (code "24") (name "NRST") (class "Default")
      (node (ref "R16") (pin "2") (pinfunction "2_2") (pintype "passive"))
      (node (ref "TP9") (pin "1") (pinfunction "P$1_1") (pintype "bidirectional"))
      (node (ref "U2") (pin "E21") (pinfunction "NRST_E21") (pintype "input"))
    )
    (net (code "25") (name "Net-(C13-Pad-)") (class "Default")
      (node (ref "C13") (pin "-") (pinfunction "-_-") (pintype "passive"))
      (node (ref "C14") (pin "-") (pinfunction "-_-") (pintype "passive"))
      (node (ref "R19") (pin "2") (pinfunction "2_2") (pintype "passive"))
    )
    (net (code "26") (name "Net-(C14-Pad+)") (class "Default")
      (node (ref "C14") (pin "+") (pinfunction "+_+") (pintype "passive"))
      (node (ref "R18") (pin "1") (pinfunction "1_1") (pintype "passive"))
      (node (ref "R29") (pin "1") (pinfunction "1_1") (pintype "passive"))
    )
    (net (code "27") (name "Net-(C16-Pad2)") (class "Default")
      (node (ref "C16") (pin "2") (pinfunction "2_2") (pintype "passive"))
      (node (ref "R21") (pin "2") (pinfunction "2_2") (pintype "passive"))
    )
    (net (code "28") (name "Net-(C17-Pad1)") (class "Default")
      (node (ref "C17") (pin "1") (pinfunction "1_1") (pintype "passive"))
      (node (ref "R20") (pin "1") (pinfunction "1_1") (pintype "passive"))
      (node (ref "R30") (pin "1") (pinfunction "1_1") (pintype "passive"))
    )
    (net (code "29") (name "Net-(J4H-S)") (class "Default")
      (node (ref "J4") (pin "7") (pinfunction "S_7") (pintype "bidirectional"))
      (node (ref "J4") (pin "8") (pinfunction "S_8") (pintype "bidirectional"))
      (node (ref "J8") (pin "1") (pinfunction "V+_1") (pintype "bidirectional"))
    )
    (net (code "30") (name "Net-(J6-5V)") (class "Default")
      (node (ref "C3") (pin "1") (pinfunction "1_1") (pintype "passive"))
      (node (ref "DA1") (pin "4") (pinfunction "4_4") (pintype "passive"))
      (node (ref "J6") (pin "1") (pinfunction "5V_1") (pintype "power_in"))
      (node (ref "L1") (pin "2") (pinfunction "2_2") (pintype "passive"))
    )
    (net (code "31") (name "Net-(TP1-P$1)") (class "Default")
      (node (ref "TP1") (pin "1") (pinfunction "P$1_1") (pintype "bidirectional"))
      (node (ref "U2") (pin "E20") (pinfunction "VBAT_E20") (pintype "power_in"))
    )
    (net (code "32") (name "Net-(TP7-P$1)") (class "Default")
      (node (ref "C13") (pin "+") (pinfunction "+_+") (pintype "passive"))
      (node (ref "C16") (pin "1") (pinfunction "1_1") (pintype "passive"))
      (node (ref "TP7") (pin "1") (pinfunction "P$1_1") (pintype "bidirectional"))
      (node (ref "U3") (pin "14") (pinfunction "VOUTL_14") (pintype "bidirectional"))
    )
    (net (code "33") (name "Net-(U2-PA9{slash}DRXD)") (class "Default")
      (node (ref "U2") (pin "S14") (pinfunction "PA9/DRXD_S14") (pintype "bidirectional"))
      (node (ref "W2") (pin "1") (pinfunction "P$1_1") (pintype "bidirectional"))
    )
    (net (code "34") (name "Net-(U2-PA10{slash}DTXD)") (class "Default")
      (node (ref "U2") (pin "S13") (pinfunction "PA10/DTXD_S13") (pintype "bidirectional"))
      (node (ref "W3") (pin "1") (pinfunction "P$1_1") (pintype "bidirectional"))
    )
    (net (code "35") (name "Net-(U3-D+)") (class "Default")
      (node (ref "R2") (pin "2") (pinfunction "2_2") (pintype "passive"))
      (node (ref "U3") (pin "9") (pinfunction "D+_9") (pintype "bidirectional"))
    )
    (net (code "36") (name "Net-(U3-D-)") (class "Default")
      (node (ref "R1") (pin "2") (pinfunction "2_2") (pintype "passive"))
      (node (ref "U3") (pin "8") (pinfunction "D-_8") (pintype "bidirectional"))
    )
    (net (code "37") (name "Net-(U3-DT)") (class "Default")
      (node (ref "R14") (pin "2") (pinfunction "2_2") (pintype "passive"))
      (node (ref "U3") (pin "3") (pinfunction "DT_3") (pintype "bidirectional"))
    )
    (net (code "38") (name "Net-(U3-VCCL)") (class "Default")
      (node (ref "C11") (pin "1") (pinfunction "1_1") (pintype "passive"))
      (node (ref "U3") (pin "13") (pinfunction "VCCL_13") (pintype "bidirectional"))
    )
    (net (code "39") (name "Net-(U3-VCCP)") (class "Default")
      (node (ref "C7") (pin "1") (pinfunction "1_1") (pintype "passive"))
      (node (ref "U3") (pin "20") (pinfunction "VCCP_20") (pintype "bidirectional"))
    )
    (net (code "40") (name "Net-(U3-VCCR)") (class "Default")
      (node (ref "C8") (pin "1") (pinfunction "1_1") (pintype "passive"))
      (node (ref "U3") (pin "16") (pinfunction "VCCR_16") (pintype "bidirectional"))
    )
    (net (code "41") (name "Net-(U3-VCOM)") (class "Default")
      (node (ref "C6") (pin "+") (pinfunction "+_+") (pintype "passive"))
      (node (ref "U3") (pin "18") (pinfunction "VCOM_18") (pintype "bidirectional"))
    )
    (net (code "42") (name "Net-(U3-VOUTR)") (class "Default")
      (node (ref "U3") (pin "15") (pinfunction "VOUTR_15") (pintype "bidirectional"))
      (node (ref "W1") (pin "1") (pinfunction "P$1_1") (pintype "bidirectional"))
    )
    (net (code "43") (name "Net-(U3-XTI)") (class "Default")
      (node (ref "C5") (pin "1") (pinfunction "1_1") (pintype "passive"))
      (node (ref "Q1") (pin "2") (pinfunction "2_2") (pintype "passive"))
      (node (ref "R13") (pin "2") (pinfunction "2_2") (pintype "passive"))
      (node (ref "U3") (pin "28") (pinfunction "XTI_28") (pintype "bidirectional"))
    )
    (net (code "44") (name "Net-(U3-XTO)") (class "Default")
      (node (ref "C4") (pin "1") (pinfunction "1_1") (pintype "passive"))
      (node (ref "Q1") (pin "1") (pinfunction "1_1") (pintype "passive"))
      (node (ref "R13") (pin "1") (pinfunction "1_1") (pintype "passive"))
      (node (ref "U3") (pin "1") (pinfunction "XTO_1") (pintype "bidirectional"))
    )
    (net (code "45") (name "Net-(U4-IN+)") (class "Default")
      (node (ref "R18") (pin "2") (pinfunction "2_2") (pintype "passive"))
      (node (ref "R29") (pin "2") (pinfunction "2_2") (pintype "passive"))
      (node (ref "U4") (pin "3") (pinfunction "IN+_3") (pintype "bidirectional"))
    )
    (net (code "46") (name "Net-(U4-IN-)") (class "Default")
      (node (ref "R20") (pin "2") (pinfunction "2_2") (pintype "passive"))
      (node (ref "R30") (pin "2") (pinfunction "2_2") (pintype "passive"))
      (node (ref "U4") (pin "4") (pinfunction "IN-_4") (pintype "bidirectional"))
    )
    (net (code "47") (name "Net-(U4-VO+)") (class "Default")
      (node (ref "L6") (pin "1") (pinfunction "1_1") (pintype "passive"))
      (node (ref "U4") (pin "5") (pinfunction "VO+_5") (pintype "bidirectional"))
    )
    (net (code "48") (name "Net-(U4-VO-)") (class "Default")
      (node (ref "L7") (pin "1") (pinfunction "1_1") (pintype "passive"))
      (node (ref "U4") (pin "8") (pinfunction "VO-_8") (pintype "bidirectional"))
    )
    (net (code "49") (name "Net-(U5-BST)") (class "Default")
      (node (ref "C21") (pin "1") (pinfunction "1_1") (pintype "passive"))
      (node (ref "U5") (pin "1") (pinfunction "BST_1") (pintype "bidirectional"))
    )
    (net (code "50") (name "Net-(U5-SW)") (class "Default")
      (node (ref "C21") (pin "2") (pinfunction "2_2") (pintype "passive"))
      (node (ref "D1") (pin "K") (pinfunction "K_K") (pintype "passive"))
      (node (ref "L3") (pin "1") (pinfunction "1_1") (pintype "passive"))
      (node (ref "U5") (pin "8") (pinfunction "SW_8") (pintype "bidirectional"))
    )
    (net (code "51") (name "Net-(U6-BST)") (class "Default")
      (node (ref "C24") (pin "1") (pinfunction "1_1") (pintype "passive"))
      (node (ref "U6") (pin "1") (pinfunction "BST_1") (pintype "bidirectional"))
    )
    (net (code "52") (name "Net-(U6-SW)") (class "Default")
      (node (ref "C24") (pin "2") (pinfunction "2_2") (pintype "passive"))
      (node (ref "D2") (pin "K") (pinfunction "K_K") (pintype "passive"))
      (node (ref "L2") (pin "1") (pinfunction "1_1") (pintype "passive"))
      (node (ref "U6") (pin "8") (pinfunction "SW_8") (pintype "bidirectional"))
    )
    (net (code "53") (name "Net-(U8-~{RST})") (class "Default")
      (node (ref "R16") (pin "1") (pinfunction "1_1") (pintype "passive"))
      (node (ref "U8") (pin "2") (pinfunction "~{RST}_2") (pintype "open_collector"))
    )
    (net (code "54") (name "PC18{slash}PWM0") (class "Default")
      (node (ref "J2") (pin "10") (pinfunction "S_10") (pintype "bidirectional"))
      (node (ref "U2") (pin "N20") (pinfunction "PC18/PWM0_N20") (pintype "bidirectional"))
    )
    (net (code "55") (name "PC19{slash}PWM1") (class "Default")
      (node (ref "J2") (pin "12") (pinfunction "S_12") (pintype "bidirectional"))
      (node (ref "U2") (pin "N21") (pinfunction "PC19/PWM1_N21") (pintype "bidirectional"))
    )
    (net (code "56") (name "PC20{slash}PWM2") (class "Default")
      (node (ref "J2") (pin "11") (pinfunction "S_11") (pintype "bidirectional"))
      (node (ref "U2") (pin "N22") (pinfunction "PC20/PWM2_N22") (pintype "bidirectional"))
    )
    (net (code "57") (name "PC22{slash}TXD3") (class "Default")
      (node (ref "J2") (pin "13") (pinfunction "S_13") (pintype "bidirectional"))
      (node (ref "U2") (pin "E2") (pinfunction "PC22/TXD3_E2") (pintype "bidirectional"))
    )
    (net (code "58") (name "PC23{slash}RXD3") (class "Default")
      (node (ref "J2") (pin "15") (pinfunction "S_15") (pintype "bidirectional"))
      (node (ref "U2") (pin "E3") (pinfunction "PC23/RXD3_E3") (pintype "bidirectional"))
    )
    (net (code "59") (name "PC24{slash}RTS3") (class "Default")
      (node (ref "J2") (pin "17") (pinfunction "S_17") (pintype "bidirectional"))
      (node (ref "U2") (pin "E4") (pinfunction "PC24/RTS3_E4") (pintype "bidirectional"))
    )
    (net (code "60") (name "PC25{slash}CTS3") (class "Default")
      (node (ref "J2") (pin "19") (pinfunction "S_19") (pintype "bidirectional"))
      (node (ref "U2") (pin "E5") (pinfunction "PC25/CTS3_E5") (pintype "bidirectional"))
    )
    (net (code "61") (name "SCL0") (class "Default")
      (node (ref "J2") (pin "8") (pinfunction "S_8") (pintype "bidirectional"))
      (node (ref "J4") (pin "2") (pinfunction "S_2") (pintype "bidirectional"))
      (node (ref "R4") (pin "2") (pinfunction "2_2") (pintype "passive"))
      (node (ref "U2") (pin "W18") (pinfunction "PA31/SCL0_W18") (pintype "bidirectional"))
      (node (ref "U9") (pin "2") (pinfunction "SCL_2") (pintype "bidirectional"))
    )
    (net (code "62") (name "SDA0") (class "Default")
      (node (ref "J2") (pin "6") (pinfunction "S_6") (pintype "bidirectional"))
      (node (ref "J4") (pin "4") (pinfunction "S_4") (pintype "bidirectional"))
      (node (ref "R3") (pin "2") (pinfunction "2_2") (pintype "passive"))
      (node (ref "U2") (pin "W17") (pinfunction "PA30/SDA0_W17") (pintype "bidirectional"))
      (node (ref "U9") (pin "1") (pinfunction "SDA_1") (pintype "bidirectional"))
    )
    (net (code "63") (name "SD_CLK") (class "Default")
      (node (ref "J3") (pin "5") (pinfunction "CLK_5") (pintype "input"))
      (node (ref "U2") (pin "S6") (pinfunction "PA17/SD_CK_S6") (pintype "bidirectional"))
    )
    (net (code "64") (name "SD_CMD") (class "Default")
      (node (ref "J3") (pin "3") (pinfunction "CMD_3") (pintype "input"))
      (node (ref "U2") (pin "S7") (pinfunction "PA16/SD_CDA_S7") (pintype "bidirectional"))
    )
    (net (code "65") (name "SD_DAT0") (class "Default")
      (node (ref "J3") (pin "7") (pinfunction "DAT0_7") (pintype "bidirectional"))
      (node (ref "U2") (pin "S8") (pinfunction "PA15/SD_DA0_S8") (pintype "bidirectional"))
    )
    (net (code "66") (name "SD_DAT1") (class "Default")
      (node (ref "J3") (pin "8") (pinfunction "DAT1_8") (pintype "bidirectional"))
      (node (ref "U2") (pin "S5") (pinfunction "PA18/SD_DA1_S5") (pintype "bidirectional"))
    )
    (net (code "67") (name "SD_DAT2") (class "Default")
      (node (ref "J3") (pin "1") (pinfunction "DAT2_1") (pintype "bidirectional"))
      (node (ref "U2") (pin "S4") (pinfunction "PA19/SD_DA2_S4") (pintype "bidirectional"))
    )
    (net (code "68") (name "SD_DAT3") (class "Default")
      (node (ref "J3") (pin "2") (pinfunction "CD/DAT3_2") (pintype "bidirectional"))
      (node (ref "U2") (pin "S3") (pinfunction "PA20/SD_DA3_S3") (pintype "bidirectional"))
    )
    (net (code "69") (name "SPCK") (class "Default")
      (node (ref "J2") (pin "16") (pinfunction "S_16") (pintype "bidirectional"))
      (node (ref "U2") (pin "S11") (pinfunction "PA12/SPCK_S11") (pintype "bidirectional"))
    )
    (net (code "70") (name "SPI_CS0") (class "Default")
      (node (ref "J2") (pin "14") (pinfunction "S_14") (pintype "bidirectional"))
      (node (ref "U2") (pin "S12") (pinfunction "PA11/NPCS0_S12") (pintype "bidirectional"))
    )
    (net (code "71") (name "SPK+") (class "Default")
      (node (ref "C33") (pin "1") (pinfunction "1_1") (pintype "passive"))
      (node (ref "J7") (pin "10") (pinfunction "S_10") (pintype "bidirectional"))
      (node (ref "L6") (pin "2") (pinfunction "2_2") (pintype "passive"))
    )
    (net (code "72") (name "SPK-") (class "Default")
      (node (ref "C32") (pin "1") (pinfunction "1_1") (pintype "passive"))
      (node (ref "J7") (pin "9") (pinfunction "S_9") (pintype "bidirectional"))
      (node (ref "L7") (pin "2") (pinfunction "2_2") (pintype "passive"))
    )
    (net (code "73") (name "USBA_5V") (class "Default")
      (node (ref "C1") (pin "1") (pinfunction "1_1") (pintype "passive"))
      (node (ref "C2") (pin "1") (pinfunction "1_1") (pintype "passive"))
      (node (ref "L1") (pin "1") (pinfunction "1_1") (pintype "passive"))
      (node (ref "U1") (pin "8") (pinfunction "OUT1_8") (pintype "power_in"))
    )
    (net (code "74") (name "USBA_D+") (class "Default")
      (node (ref "DA1") (pin "2") (pinfunction "2_2") (pintype "passive"))
      (node (ref "J6") (pin "3") (pinfunction "D+_3") (pintype "bidirectional"))
      (node (ref "U2") (pin "E19") (pinfunction "USBAP_E19") (pintype "bidirectional"))
    )
    (net (code "75") (name "USBA_D-") (class "Default")
      (node (ref "DA1") (pin "3") (pinfunction "3_3") (pintype "passive"))
      (node (ref "J6") (pin "2") (pinfunction "D-_2") (pintype "bidirectional"))
      (node (ref "U2") (pin "E18") (pinfunction "USBAN_E18") (pintype "bidirectional"))
    )
    (net (code "76") (name "USBB_5V") (class "Default")
      (node (ref "J1") (pin "1") (pinfunction "S_1") (pintype "bidirectional"))
      (node (ref "U1") (pin "5") (pinfunction "OUT2_5") (pintype "power_in"))
    )
    (net (code "77") (name "USBB_D+") (class "Default")
      (node (ref "J1") (pin "2") (pinfunction "S_2") (pintype "bidirectional"))
      (node (ref "U2") (pin "E16") (pinfunction "USBBP_E16") (pintype "bidirectional"))
    )
    (net (code "78") (name "USBB_D-") (class "Default")
      (node (ref "J1") (pin "3") (pinfunction "S_3") (pintype "bidirectional"))
      (node (ref "U2") (pin "E15") (pinfunction "USBBN_E15") (pintype "bidirectional"))
    )
    (net (code "79") (name "USBC_D+") (class "Default")
      (node (ref "R15") (pin "1") (pinfunction "1_1") (pintype "passive"))
      (node (ref "R2") (pin "1") (pinfunction "1_1") (pintype "passive"))
      (node (ref "U2") (pin "E12") (pinfunction "USBCP_E12") (pintype "bidirectional"))
    )
    (net (code "80") (name "USBC_D-") (class "Default")
      (node (ref "R1") (pin "1") (pinfunction "1_1") (pintype "passive"))
      (node (ref "U2") (pin "E13") (pinfunction "USBCN_E13") (pintype "bidirectional"))
    )
    (net (code "81") (name "USB_EN1") (class "Default")
      (node (ref "R8") (pin "1") (pinfunction "1_1") (pintype "passive"))
      (node (ref "U1") (pin "1") (pinfunction "~{EN1}_1") (pintype "input"))
      (node (ref "U2") (pin "W13") (pinfunction "PA26_W13") (pintype "bidirectional"))
    )
    (net (code "82") (name "USB_EN2") (class "Default")
      (node (ref "R6") (pin "1") (pinfunction "1_1") (pintype "passive"))
      (node (ref "U1") (pin "4") (pinfunction "~{EN2}_4") (pintype "input"))
      (node (ref "U2") (pin "W16") (pinfunction "PA29_W16") (pintype "bidirectional"))
    )
    (net (code "83") (name "USB_FLAG1") (class "Default")
      (node (ref "R7") (pin "1") (pinfunction "1_1") (pintype "passive"))
      (node (ref "U1") (pin "2") (pinfunction "FLAG1_2") (pintype "output"))
      (node (ref "U2") (pin "W14") (pinfunction "PA27_W14") (pintype "bidirectional"))
    )
    (net (code "84") (name "USB_FLAG2") (class "Default")
      (node (ref "R5") (pin "1") (pinfunction "1_1") (pintype "passive"))
      (node (ref "U1") (pin "3") (pinfunction "FLAG2_3") (pintype "output"))
      (node (ref "U2") (pin "W15") (pinfunction "PA28_W15") (pintype "bidirectional"))
    )
    (net (code "85") (name "VREF") (class "Default")
      (node (ref "U2") (pin "W19") (pinfunction "ADVREF_W19") (pintype "bidirectional"))
    )
    (net (code "86") (name "V_AUX_ON") (class "Default")
      (node (ref "J4") (pin "1") (pinfunction "S_1") (pintype "bidirectional"))
      (node (ref "U2") (pin "W9") (pinfunction "PA22_W9") (pintype "bidirectional"))
    )
    (net (code "87") (name "unconnected-(J3-PadDC)") (class "Default")
      (node (ref "J3") (pin "DC") (pinfunction "DC_DC") (pintype "passive"))
    )
    (net (code "88") (name "unconnected-(J3-PadDT)") (class "Default")
      (node (ref "J3") (pin "DT") (pinfunction "DT_DT") (pintype "bidirectional"))
    )
    (net (code "89") (name "unconnected-(J7C-S-Pad2)") (class "Default")
      (node (ref "J7") (pin "2") (pinfunction "S_2") (pintype "bidirectional"))
    )
    (net (code "90") (name "unconnected-(J9-S-Pad1)") (class "Default")
      (node (ref "J9") (pin "1") (pinfunction "S_1") (pintype "bidirectional"))
    )
    (net (code "91") (name "unconnected-(J10-S-Pad1)") (class "Default")
      (node (ref "J10") (pin "1") (pinfunction "S_1") (pintype "bidirectional"))
    )
    (net (code "92") (name "unconnected-(J11-S-Pad1)") (class "Default")
      (node (ref "J11") (pin "1") (pinfunction "S_1") (pintype "bidirectional"))
    )
    (net (code "93") (name "unconnected-(U2-PA0{slash}TXD0-PadS23)") (class "Default")
      (node (ref "U2") (pin "S23") (pinfunction "PA0/TXD0_S23") (pintype "bidirectional"))
    )
    (net (code "94") (name "unconnected-(U2-PA1{slash}RXD0-PadS22)") (class "Default")
      (node (ref "U2") (pin "S22") (pinfunction "PA1/RXD0_S22") (pintype "bidirectional"))
    )
    (net (code "95") (name "unconnected-(U2-PA2{slash}RTS0-PadS21)") (class "Default")
      (node (ref "U2") (pin "S21") (pinfunction "PA2/RTS0_S21") (pintype "bidirectional"))
    )
    (net (code "96") (name "unconnected-(U2-PA3{slash}CTS0-PadS20)") (class "Default")
      (node (ref "U2") (pin "S20") (pinfunction "PA3/CTS0_S20") (pintype "bidirectional"))
    )
    (net (code "97") (name "unconnected-(U2-PA4-PadS19)") (class "Default")
      (node (ref "U2") (pin "S19") (pinfunction "PA4_S19") (pintype "bidirectional"))
    )
    (net (code "98") (name "unconnected-(U2-PA5{slash}TXD1-PadS18)") (class "Default")
      (node (ref "U2") (pin "S18") (pinfunction "PA5/TXD1_S18") (pintype "bidirectional"))
    )
    (net (code "99") (name "unconnected-(U2-PA6{slash}RXD1-PadS17)") (class "Default")
      (node (ref "U2") (pin "S17") (pinfunction "PA6/RXD1_S17") (pintype "bidirectional"))
    )
    (net (code "100") (name "unconnected-(U2-PA7{slash}TXD2-PadS16)") (class "Default")
      (node (ref "U2") (pin "S16") (pinfunction "PA7/TXD2_S16") (pintype "bidirectional"))
    )
    (net (code "101") (name "unconnected-(U2-PA8{slash}RXD2-PadS15)") (class "Default")
      (node (ref "U2") (pin "S15") (pinfunction "PA8/RXD2_S15") (pintype "bidirectional"))
    )
    (net (code "102") (name "unconnected-(U2-PA21{slash}1WIRE-PadS2)") (class "Default")
      (node (ref "U2") (pin "S2") (pinfunction "PA21/1WIRE_S2") (pintype "bidirectional"))
    )
    (net (code "103") (name "unconnected-(U2-PA23-PadW10)") (class "Default")
      (node (ref "U2") (pin "W10") (pinfunction "PA23_W10") (pintype "bidirectional"))
    )
    (net (code "104") (name "unconnected-(U2-PA24-PadW11)") (class "Default")
      (node (ref "U2") (pin "W11") (pinfunction "PA24_W11") (pintype "bidirectional"))
    )
    (net (code "105") (name "unconnected-(U2-PA25-PadW12)") (class "Default")
      (node (ref "U2") (pin "W12") (pinfunction "PA25_W12") (pintype "bidirectional"))
    )
    (net (code "106") (name "unconnected-(U2-PB13{slash}AD2-PadW22)") (class "Default")
      (node (ref "U2") (pin "W22") (pinfunction "PB13/AD2_W22") (pintype "bidirectional"))
    )
    (net (code "107") (name "unconnected-(U2-PB14{slash}AD3-PadW23)") (class "Default")
      (node (ref "U2") (pin "W23") (pinfunction "PB14/AD3_W23") (pintype "bidirectional"))
    )
    (net (code "108") (name "unconnected-(U2-PC0{slash}SDA1-PadN2)") (class "Default")
      (node (ref "U2") (pin "N2") (pinfunction "PC0/SDA1_N2") (pintype "bidirectional"))
    )
    (net (code "109") (name "unconnected-(U2-PC1{slash}SCL1-PadN3)") (class "Default")
      (node (ref "U2") (pin "N3") (pinfunction "PC1/SCL1_N3") (pintype "bidirectional"))
    )
    (net (code "110") (name "unconnected-(U2-PC2-PadN4)") (class "Default")
      (node (ref "U2") (pin "N4") (pinfunction "PC2_N4") (pintype "bidirectional"))
    )
    (net (code "111") (name "unconnected-(U2-PC3-PadN5)") (class "Default")
      (node (ref "U2") (pin "N5") (pinfunction "PC3_N5") (pintype "bidirectional"))
    )
    (net (code "112") (name "unconnected-(U2-PC4-PadN6)") (class "Default")
      (node (ref "U2") (pin "N6") (pinfunction "PC4_N6") (pintype "bidirectional"))
    )
    (net (code "113") (name "unconnected-(U2-PC5-PadN7)") (class "Default")
      (node (ref "U2") (pin "N7") (pinfunction "PC5_N7") (pintype "bidirectional"))
    )
    (net (code "114") (name "unconnected-(U2-PC6-PadN8)") (class "Default")
      (node (ref "U2") (pin "N8") (pinfunction "PC6_N8") (pintype "bidirectional"))
    )
    (net (code "115") (name "unconnected-(U2-PC7-PadN9)") (class "Default")
      (node (ref "U2") (pin "N9") (pinfunction "PC7_N9") (pintype "bidirectional"))
    )
    (net (code "116") (name "unconnected-(U2-PC8{slash}UTXD0-PadN10)") (class "Default")
      (node (ref "U2") (pin "N10") (pinfunction "PC8/UTXD0_N10") (pintype "bidirectional"))
    )
    (net (code "117") (name "unconnected-(U2-PC9{slash}URXD0-PadN11)") (class "Default")
      (node (ref "U2") (pin "N11") (pinfunction "PC9/URXD0_N11") (pintype "bidirectional"))
    )
    (net (code "118") (name "unconnected-(U2-PC10-PadN12)") (class "Default")
      (node (ref "U2") (pin "N12") (pinfunction "PC10_N12") (pintype "bidirectional"))
    )
    (net (code "119") (name "unconnected-(U2-PC11-PadN13)") (class "Default")
      (node (ref "U2") (pin "N13") (pinfunction "PC11_N13") (pintype "bidirectional"))
    )
    (net (code "120") (name "unconnected-(U2-PC12-PadN14)") (class "Default")
      (node (ref "U2") (pin "N14") (pinfunction "PC12_N14") (pintype "bidirectional"))
    )
    (net (code "121") (name "unconnected-(U2-PC13-PadN15)") (class "Default")
      (node (ref "U2") (pin "N15") (pinfunction "PC13_N15") (pintype "bidirectional"))
    )
    (net (code "122") (name "unconnected-(U2-PC14-PadN16)") (class "Default")
      (node (ref "U2") (pin "N16") (pinfunction "PC14_N16") (pintype "bidirectional"))
    )
    (net (code "123") (name "unconnected-(U2-PC15-PadN17)") (class "Default")
      (node (ref "U2") (pin "N17") (pinfunction "PC15_N17") (pintype "bidirectional"))
    )
    (net (code "124") (name "unconnected-(U2-PC16{slash}UTXD1-PadN18)") (class "Default")
      (node (ref "U2") (pin "N18") (pinfunction "PC16/UTXD1_N18") (pintype "bidirectional"))
    )
    (net (code "125") (name "unconnected-(U2-PC17{slash}URXD1-PadN19)") (class "Default")
      (node (ref "U2") (pin "N19") (pinfunction "PC17/URXD1_N19") (pintype "bidirectional"))
    )
    (net (code "126") (name "unconnected-(U2-PC21{slash}PWM3-PadN23)") (class "Default")
      (node (ref "U2") (pin "N23") (pinfunction "PC21/PWM3_N23") (pintype "bidirectional"))
    )
    (net (code "127") (name "unconnected-(U2-PC26-PadE6)") (class "Default")
      (node (ref "U2") (pin "E6") (pinfunction "PC26_E6") (pintype "bidirectional"))
    )
    (net (code "128") (name "unconnected-(U2-PC27{slash}RTS1-PadE7)") (class "Default")
      (node (ref "U2") (pin "E7") (pinfunction "PC27/RTS1_E7") (pintype "bidirectional"))
    )
    (net (code "129") (name "unconnected-(U2-PC28{slash}CTS1-PadE8)") (class "Default")
      (node (ref "U2") (pin "E8") (pinfunction "PC28/CTS1_E8") (pintype "bidirectional"))
    )
    (net (code "130") (name "unconnected-(U2-PC29-PadE9)") (class "Default")
      (node (ref "U2") (pin "E9") (pinfunction "PC29_E9") (pintype "bidirectional"))
    )
    (net (code "131") (name "unconnected-(U2-PC30-PadE10)") (class "Default")
      (node (ref "U2") (pin "E10") (pinfunction "PC30_E10") (pintype "bidirectional"))
    )
    (net (code "132") (name "unconnected-(U2-PC31-PadE11)") (class "Default")
      (node (ref "U2") (pin "E11") (pinfunction "PC31_E11") (pintype "bidirectional"))
    )
    (net (code "133") (name "unconnected-(U2-SHDN-PadE22)") (class "Default")
      (node (ref "U2") (pin "E22") (pinfunction "SHDN_E22") (pintype "bidirectional"))
    )
    (net (code "134") (name "unconnected-(U2-WKUP-PadE23)") (class "Default")
      (node (ref "U2") (pin "E23") (pinfunction "WKUP_E23") (pintype "bidirectional"))
    )
    (net (code "135") (name "unconnected-(U3-CK-Pad2)") (class "Default")
      (node (ref "U3") (pin "2") (pinfunction "CK_2") (pintype "bidirectional"))
    )
    (net (code "136") (name "unconnected-(U5-PGOOD-Pad4)") (class "Default")
      (node (ref "U5") (pin "4") (pinfunction "PGOOD_4") (pintype "bidirectional"))
    )
    (net (code "137") (name "unconnected-(U6-PGOOD-Pad4)") (class "Default")
      (node (ref "U6") (pin "4") (pinfunction "PGOOD_4") (pintype "bidirectional"))
    )
    (net (code "138") (name "unconnected-(U8-~{MR}-Pad3)") (class "Default")
      (node (ref "U8") (pin "3") (pinfunction "~{MR}_3") (pintype "input"))
    )
    (net (code "139") (name "unconnected-(U9-ALERT-Pad3)") (class "Default")
      (node (ref "U9") (pin "3") (pinfunction "ALERT_3") (pintype "bidirectional"))
    )
  )
)
